# rev_n_v36.net
KiCad netlist of a schematic drawn in EAGLE
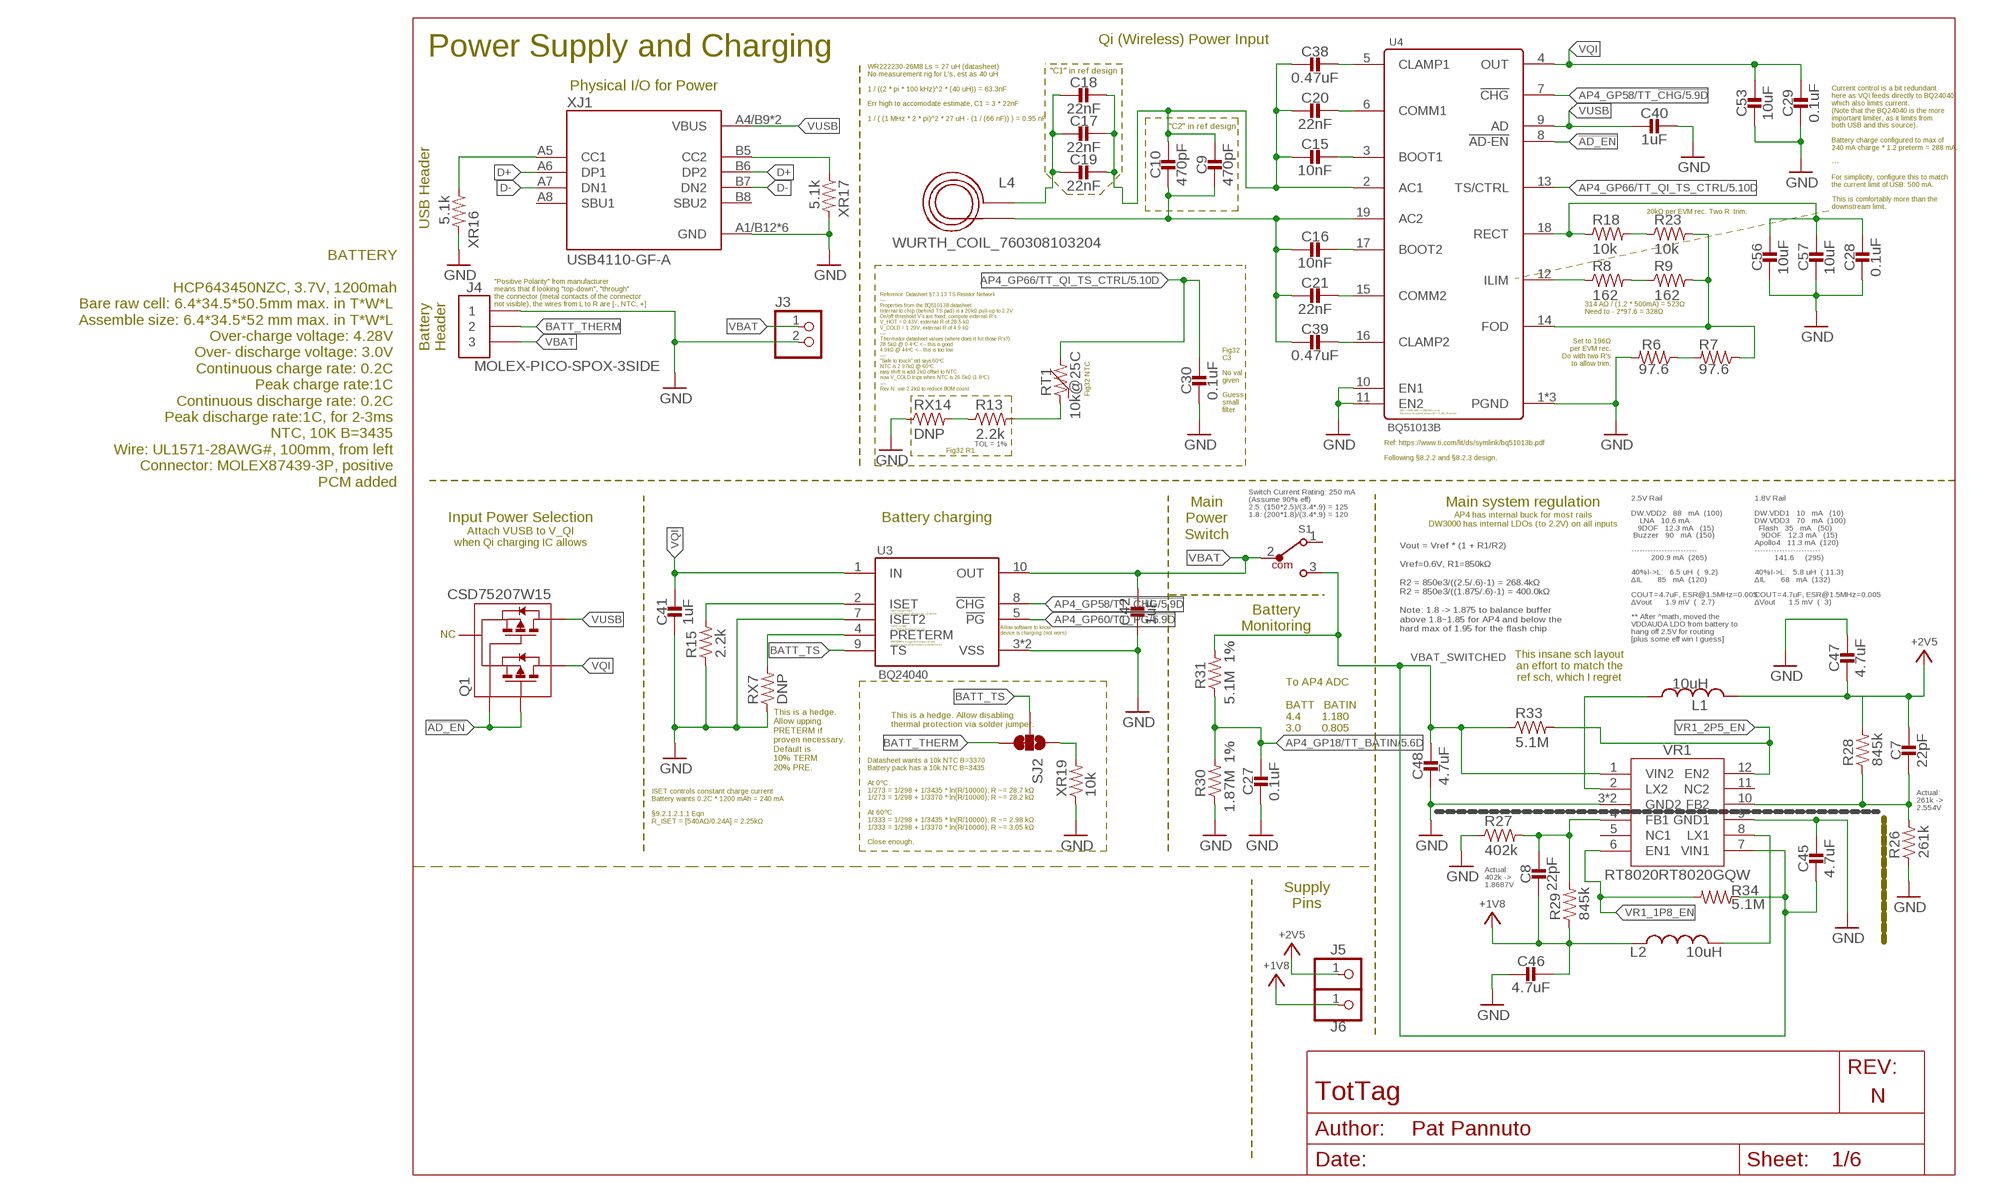
[diagram p0: schematic, sheet 1]
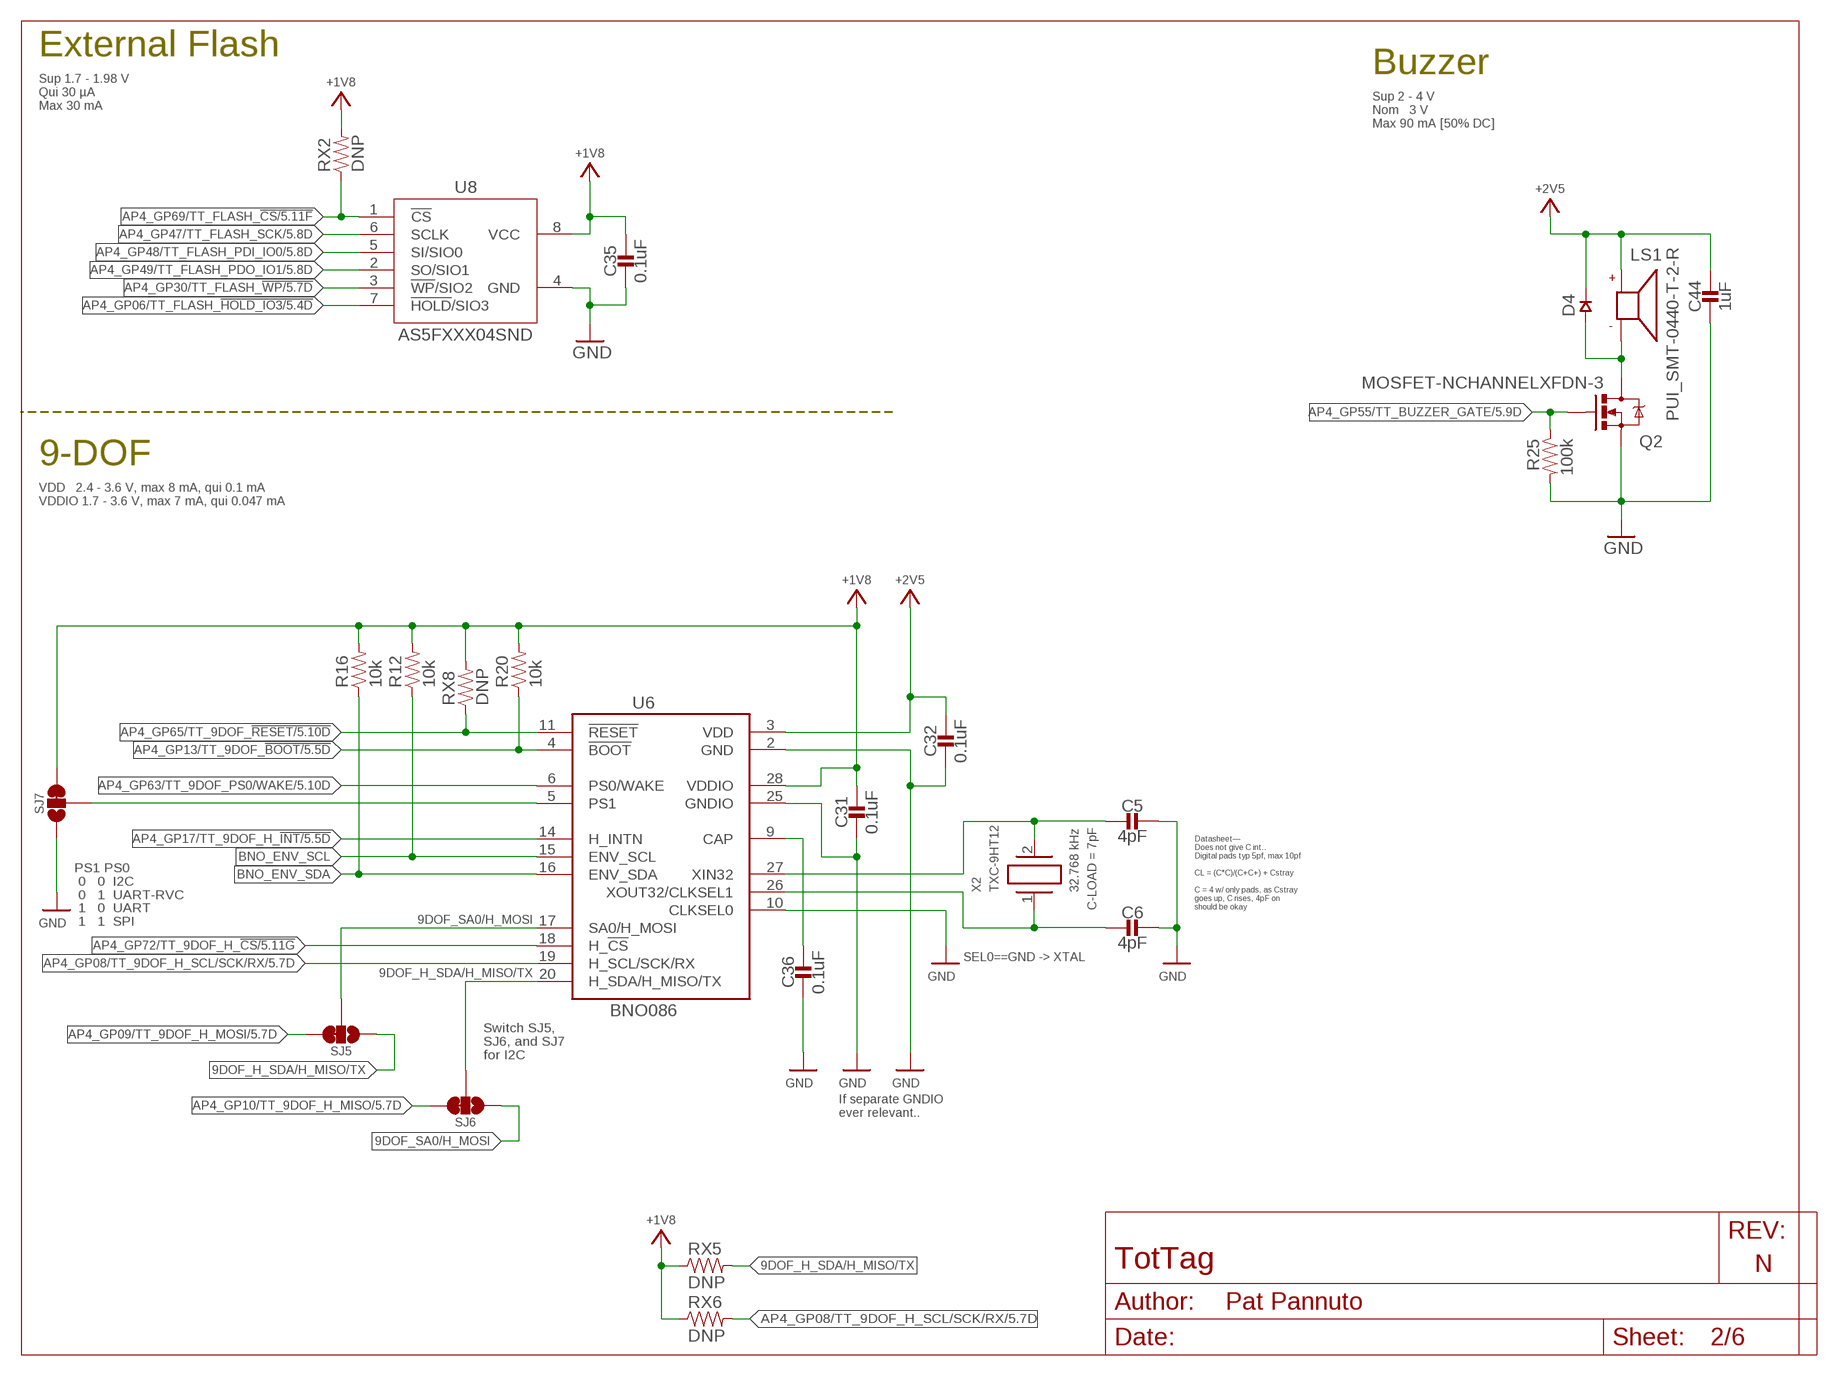
[diagram p1: schematic, sheet 2]
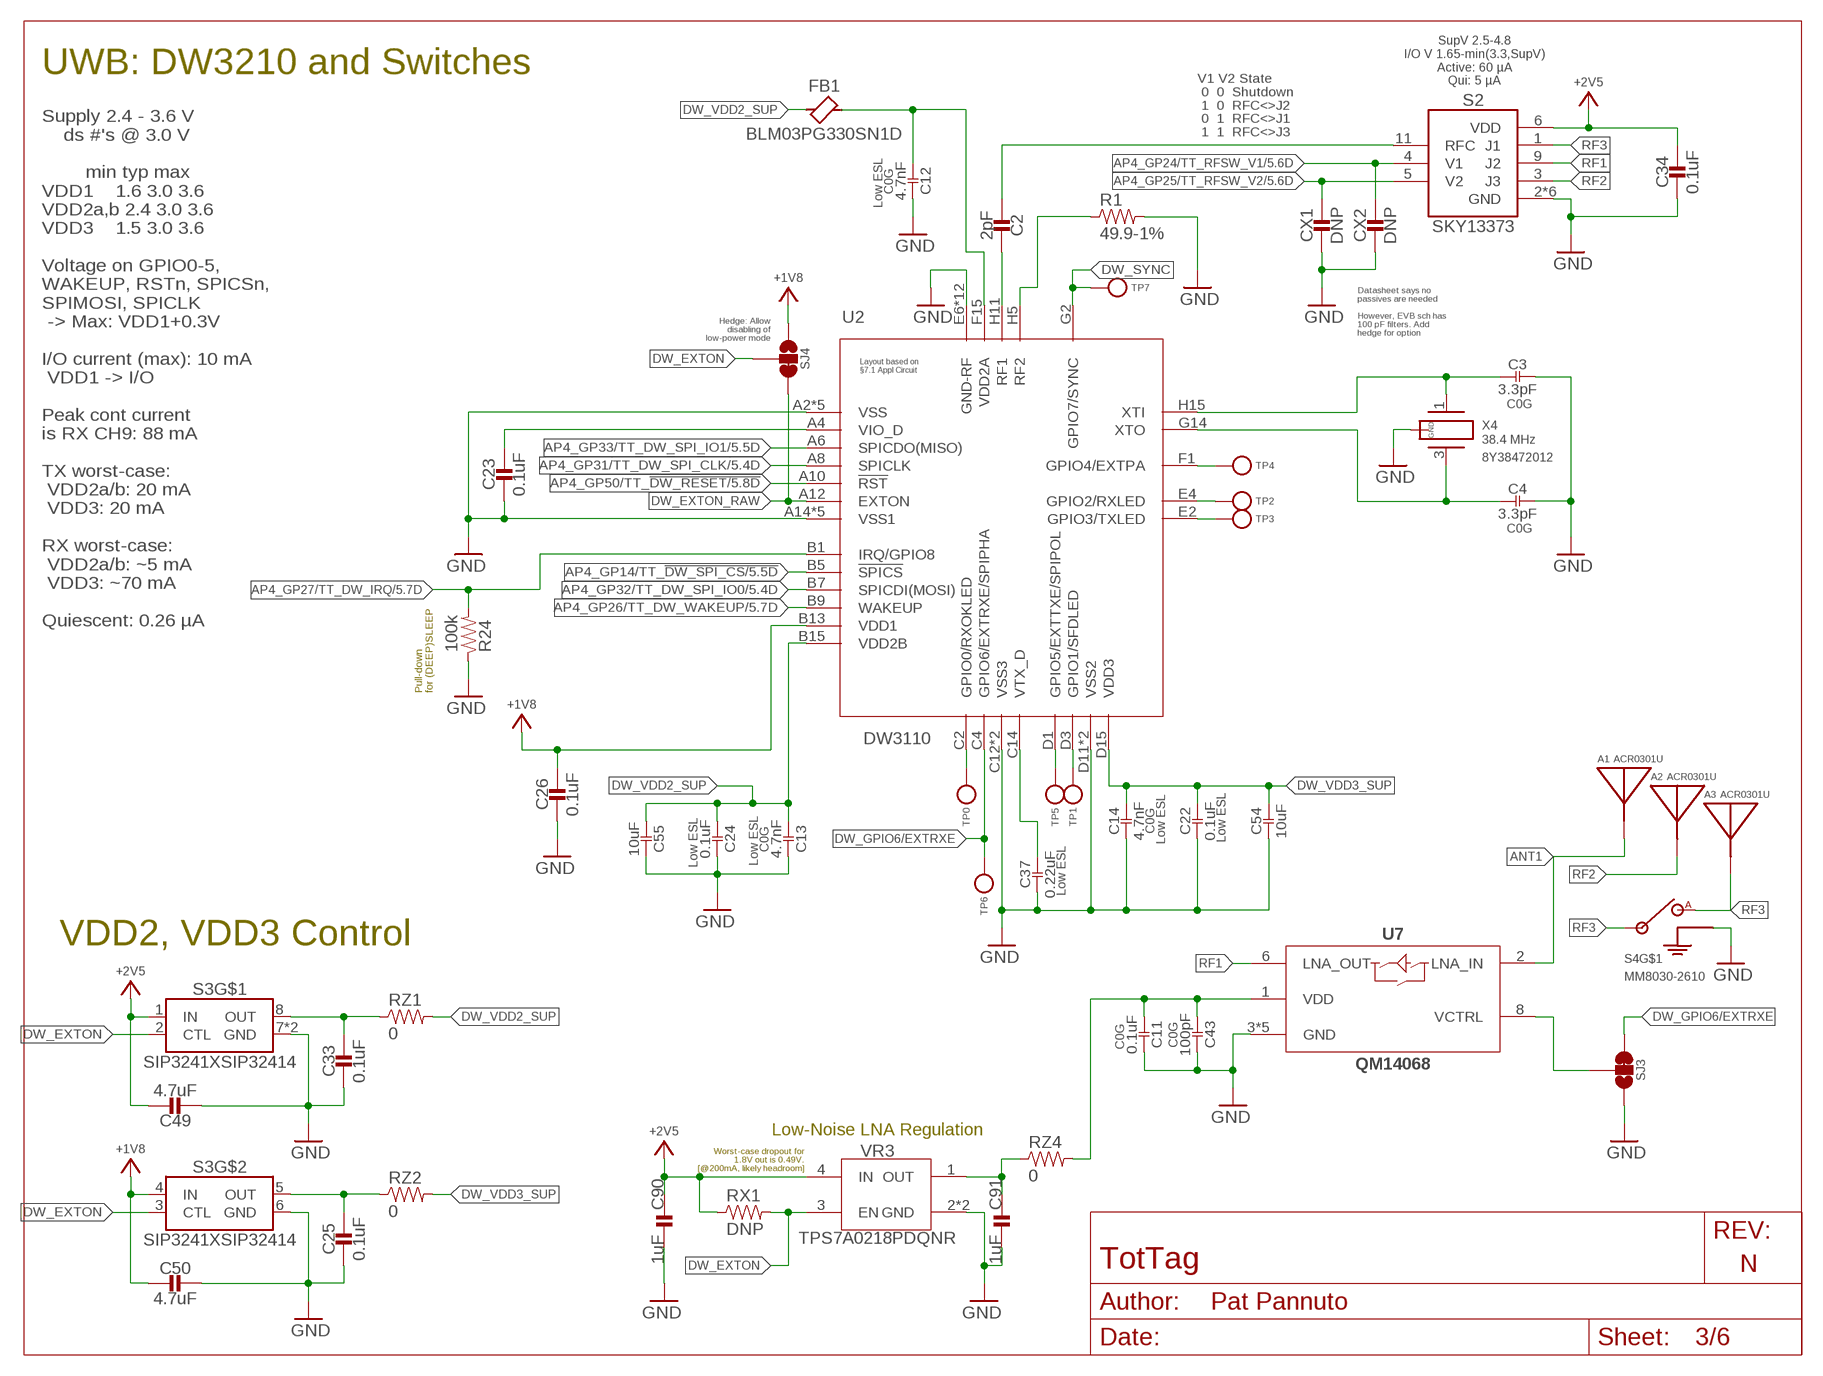
[diagram p2: schematic, sheet 3]
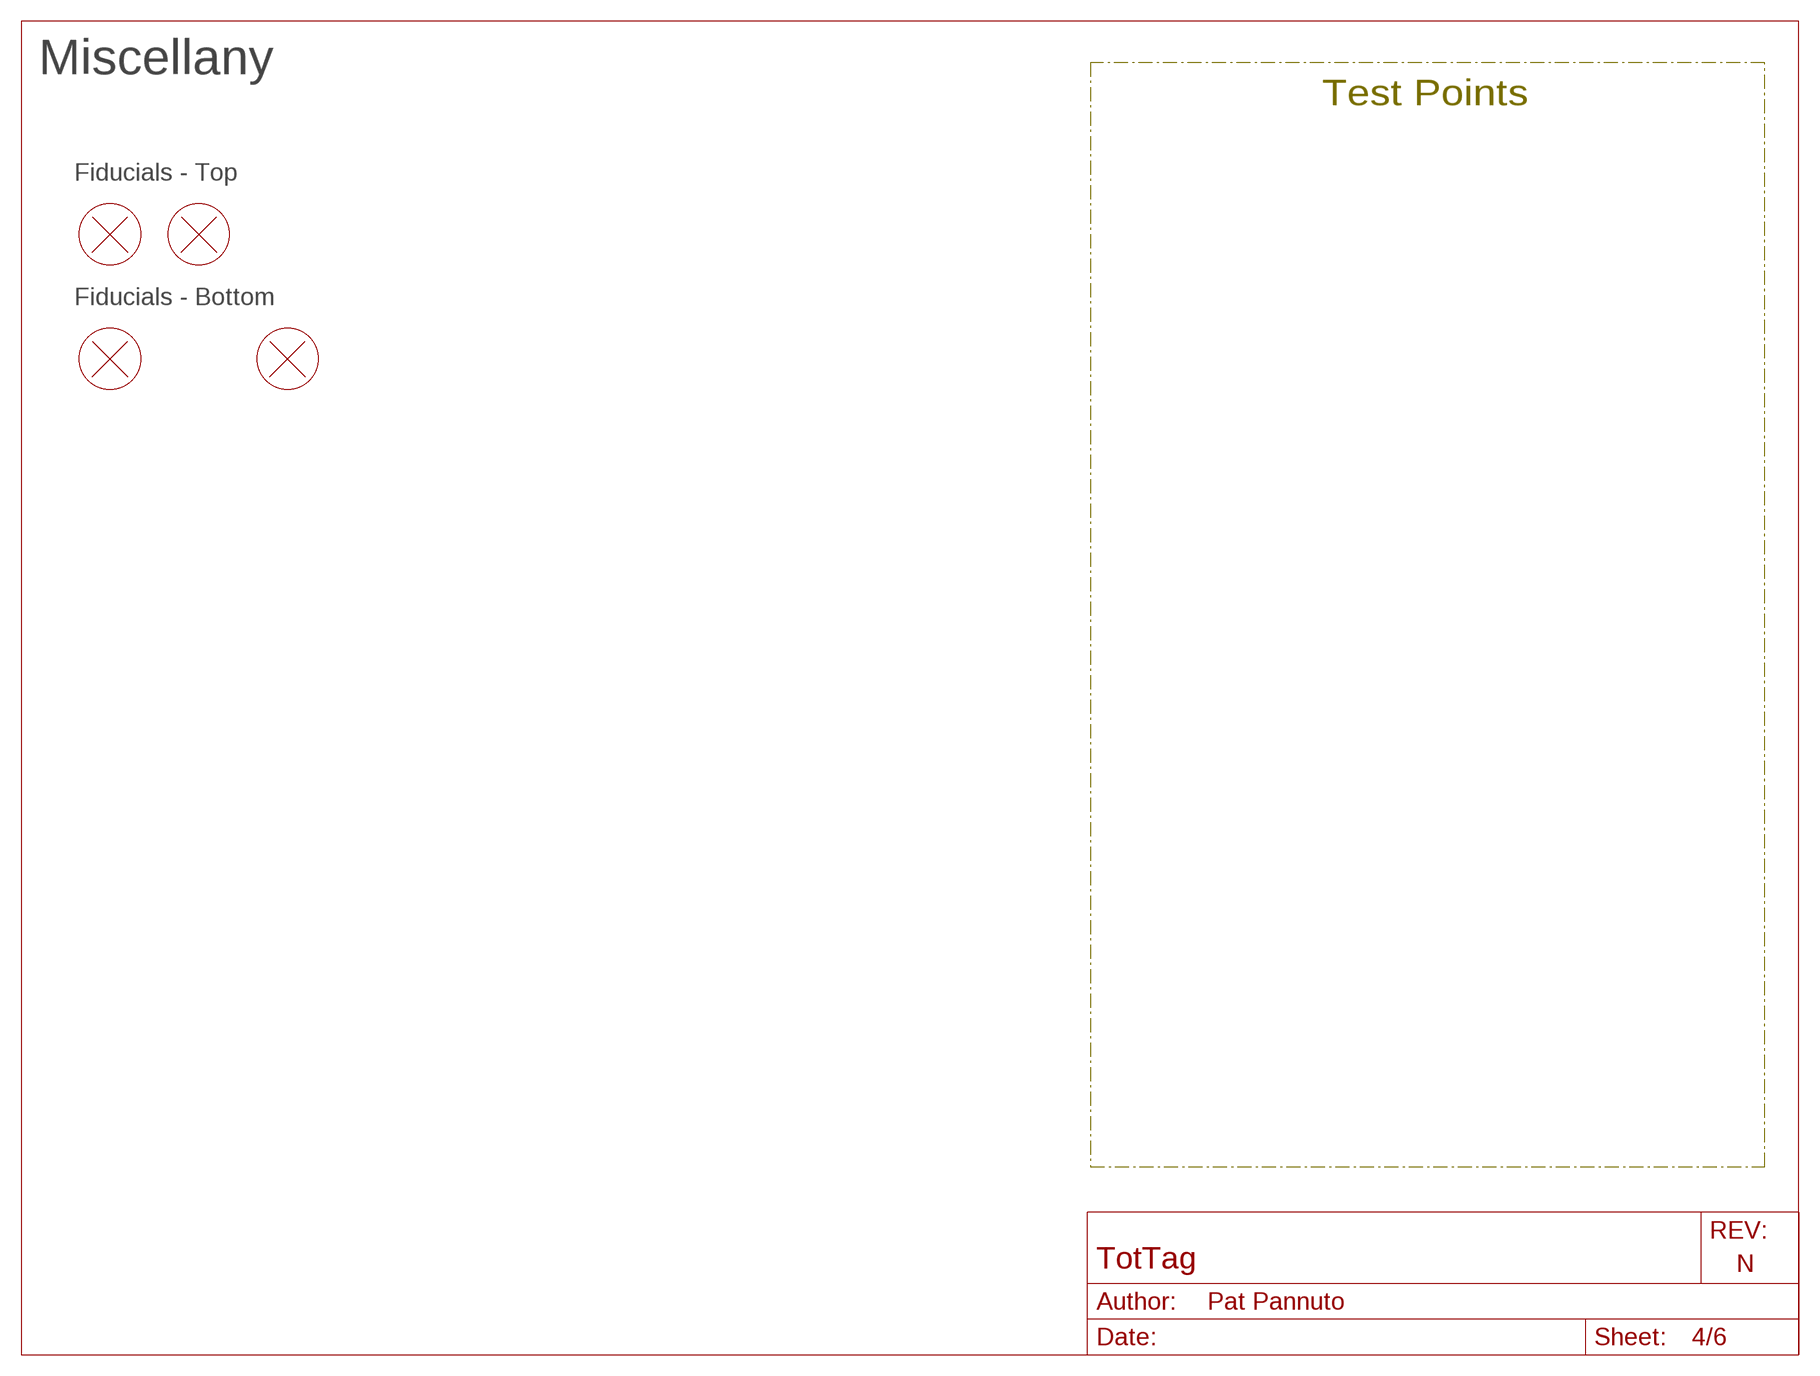
[diagram p3: schematic, sheet 4]
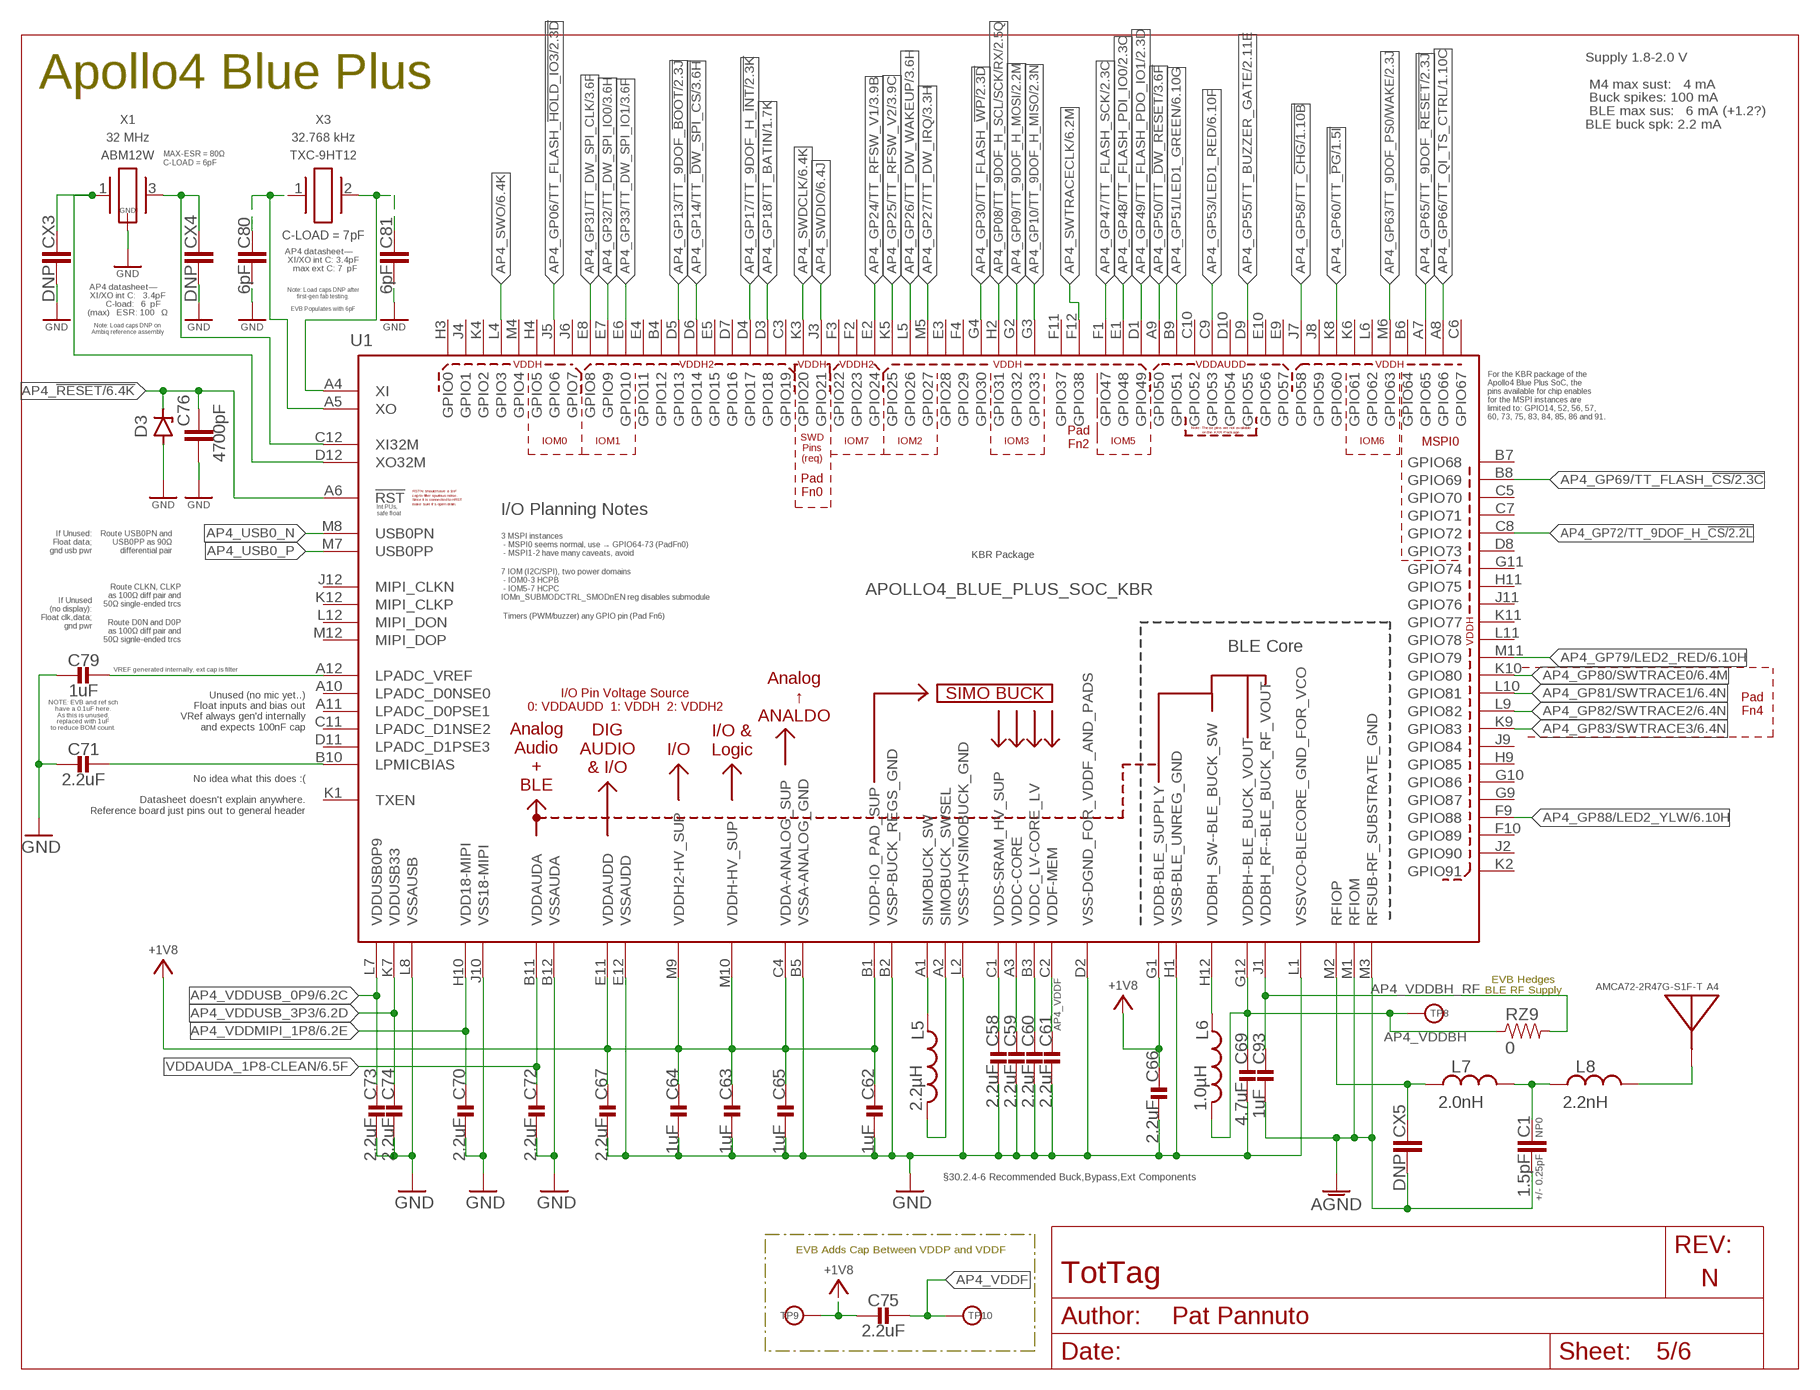
[diagram p4: schematic, sheet 5]
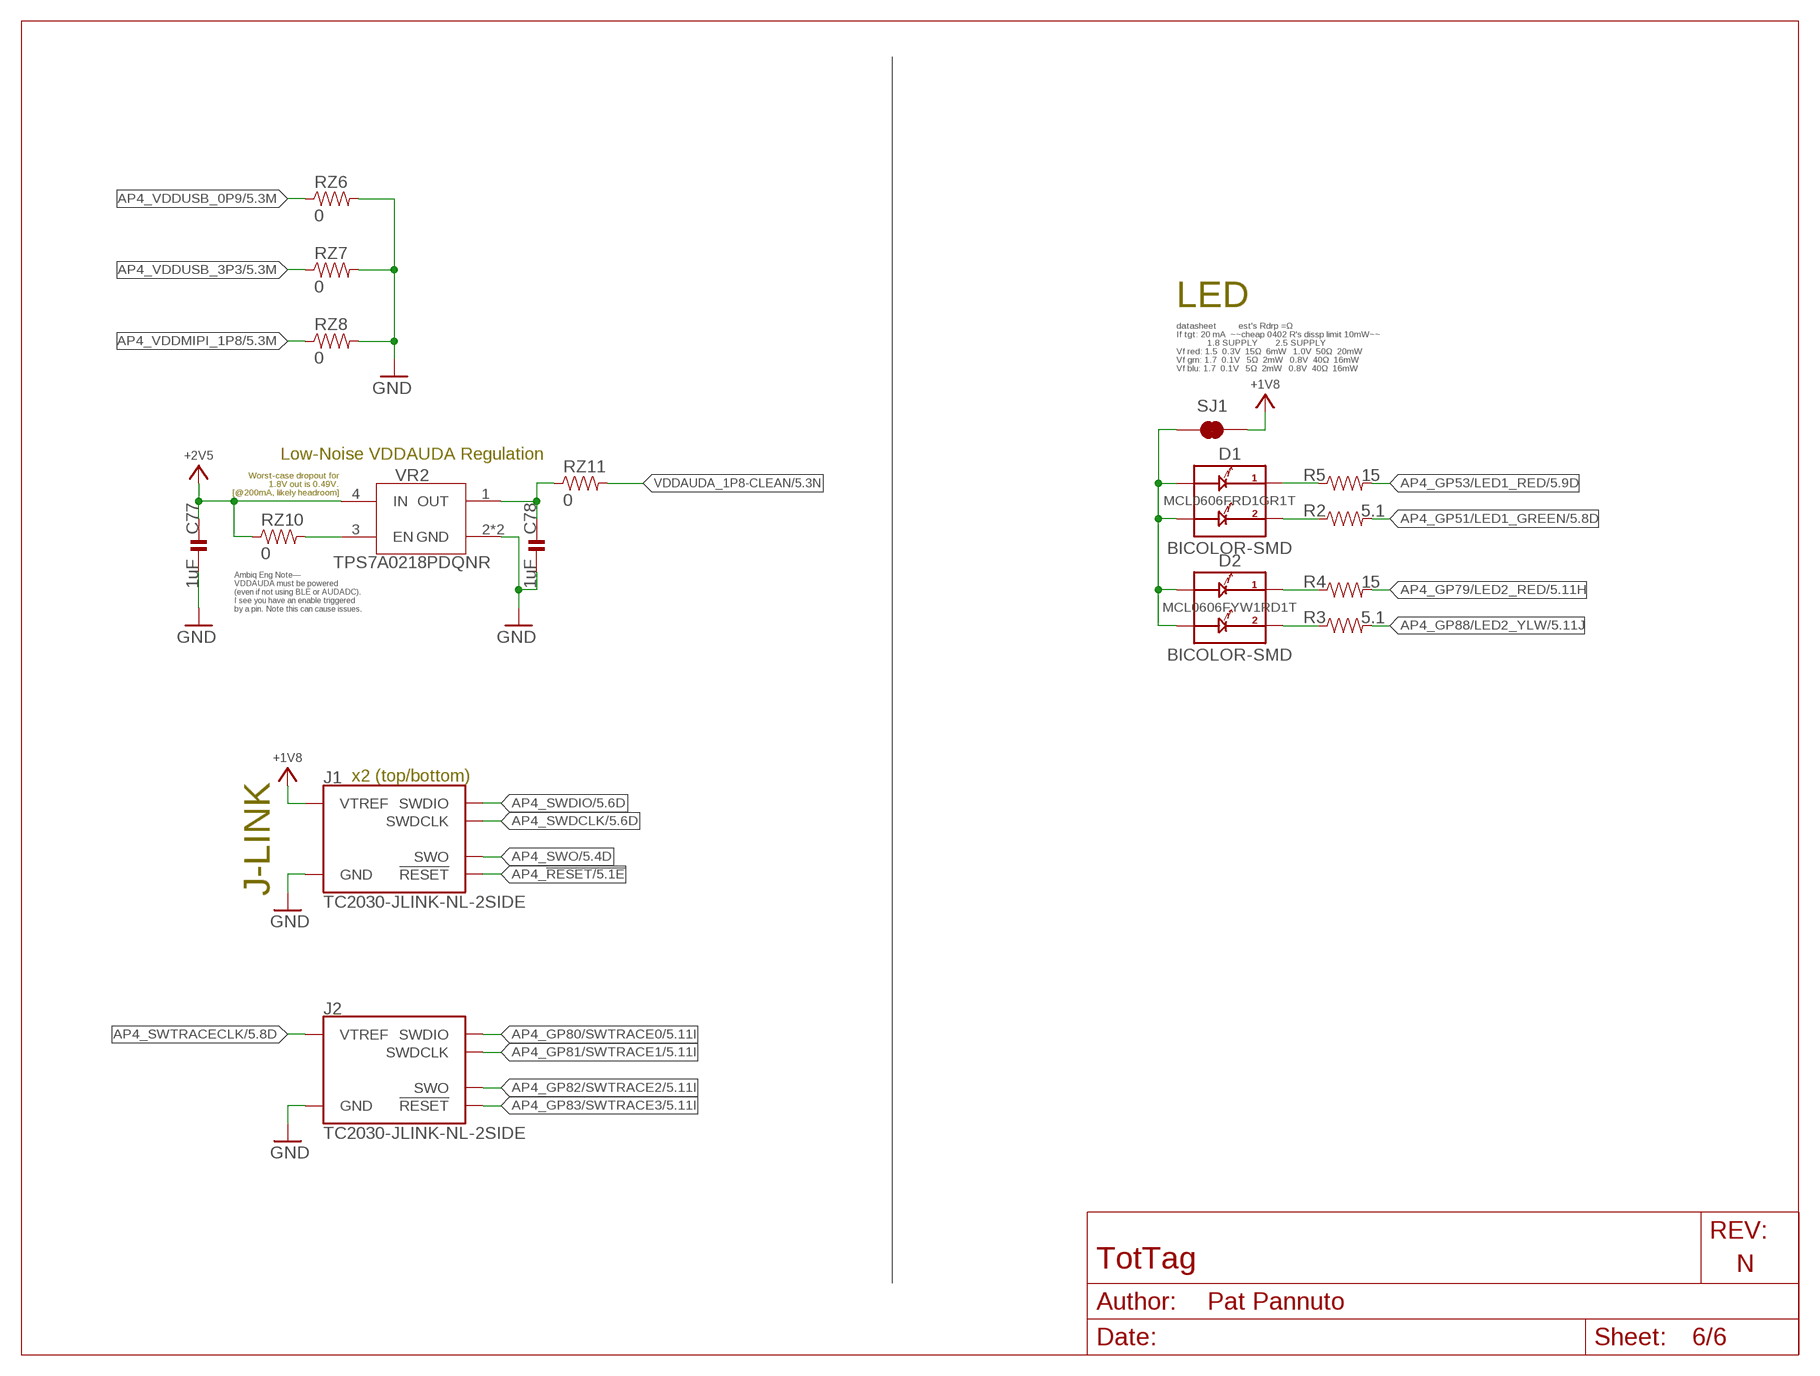
[diagram p5: schematic, sheet 6]

(export (version "E")
  (design (tool "Eeschema 10.0.6"))
  (components
    (comp (ref "C7")
      (value "22pF")
      (footprint "eagle-import:0201_CAP")
      (fields (field (name "MPN") "GRM0335C1H220FA01D"))
      (libsource (lib "eagle-import") (part "passives_20904581_CAPACITOR0201_CAP"))
    )
    (comp (ref "C8")
      (value "22pF")
      (footprint "eagle-import:0201_CAP")
      (fields (field (name "MPN") "GRM0335C1H220FA01D"))
      (libsource (lib "eagle-import") (part "passives_20904581_CAPACITOR0201_CAP"))
    )
    (comp (ref "C9")
      (value "470pF")
      (footprint "eagle-import:0402_CAP")
      (description "CAP CER 470PF 50V C0G/NP0 0402")
      (fields (field (name "MANUFACTURER") "Murata") (field (name "MPN") "GRM1555C1H471JA01J"))
      (libsource (lib "eagle-import") (part "passives_20904581_CAPACITOR0402_CAP"))
    )
    (comp (ref "C10")
      (value "470pF")
      (footprint "eagle-import:0402_CAP")
      (description "CAP CER 470PF 50V C0G/NP0 0402")
      (fields (field (name "MANUFACTURER") "Murata") (field (name "MPN") "GRM1555C1H471JA01J"))
      (libsource (lib "eagle-import") (part "passives_20904581_CAPACITOR0402_CAP"))
    )
    (comp (ref "C15")
      (value "10nF")
      (footprint "eagle-import:0402_CAP")
      (fields (field (name "MPN") "GRM155R71H103KA88J"))
      (libsource (lib "eagle-import") (part "passives_20904581_CAPACITOR0402_CAP"))
    )
    (comp (ref "C16")
      (value "10nF")
      (footprint "eagle-import:0402_CAP")
      (fields (field (name "MPN") "GRM155R71H103KA88J"))
      (libsource (lib "eagle-import") (part "passives_20904581_CAPACITOR0402_CAP"))
    )
    (comp (ref "C17")
      (value "22nF")
      (footprint "eagle-import:0402_CAP")
      (fields (field (name "MPN") "GRM155R71E223JA61D"))
      (libsource (lib "eagle-import") (part "passives_20904581_CAPACITOR0402_CAP"))
    )
    (comp (ref "C18")
      (value "22nF")
      (footprint "eagle-import:0402_CAP")
      (fields (field (name "MPN") "GRM155R71E223JA61D"))
      (libsource (lib "eagle-import") (part "passives_20904581_CAPACITOR0402_CAP"))
    )
    (comp (ref "C19")
      (value "22nF")
      (footprint "eagle-import:0402_CAP")
      (fields (field (name "MPN") "GRM155R71E223JA61D"))
      (libsource (lib "eagle-import") (part "passives_20904581_CAPACITOR0402_CAP"))
    )
    (comp (ref "C20")
      (value "22nF")
      (footprint "eagle-import:0402_CAP")
      (fields (field (name "MPN") "CC0402ZRY5V8BB223"))
      (libsource (lib "eagle-import") (part "passives_20904581_CAPACITOR0402_CAP"))
    )
    (comp (ref "C21")
      (value "22nF")
      (footprint "eagle-import:0402_CAP")
      (fields (field (name "MPN") "CC0402ZRY5V8BB223"))
      (libsource (lib "eagle-import") (part "passives_20904581_CAPACITOR0402_CAP"))
    )
    (comp (ref "C27")
      (value "0.1uF")
      (footprint "eagle-import:0402_CAP")
      (fields (field (name "MPN") "GRM155R71C104KA88J "))
      (libsource (lib "eagle-import") (part "CAPACITOR0402_CAP"))
    )
    (comp (ref "C28")
      (value "0.1uF")
      (footprint "eagle-import:0402_CAP")
      (fields (field (name "MPN") "GRM155R71C104KA88J "))
      (libsource (lib "eagle-import") (part "CAPACITOR0402_CAP"))
    )
    (comp (ref "C29")
      (value "0.1uF")
      (footprint "eagle-import:0402_CAP")
      (fields (field (name "MPN") "GRM155R71C104KA88J "))
      (libsource (lib "eagle-import") (part "CAPACITOR0402_CAP"))
    )
    (comp (ref "C30")
      (value "0.1uF")
      (footprint "eagle-import:0402_CAP")
      (fields (field (name "MPN") "GRM155R71C104KA88J "))
      (libsource (lib "eagle-import") (part "CAPACITOR0402_CAP"))
    )
    (comp (ref "C38")
      (value "0.47uF")
      (footprint "eagle-import:0402_CAP")
      (fields (field (name "MPN") "GRT155R61E474ME01D"))
      (libsource (lib "eagle-import") (part "passives_20904581_CAPACITOR0402_CAP"))
    )
    (comp (ref "C39")
      (value "0.47uF")
      (footprint "eagle-import:0402_CAP")
      (fields (field (name "MPN") "GRT155R61E474ME01D"))
      (libsource (lib "eagle-import") (part "passives_20904581_CAPACITOR0402_CAP"))
    )
    (comp (ref "C40")
      (value "1uF")
      (footprint "eagle-import:0402_CAP")
      (fields (field (name "MPN") "GRM155R70J105KA12J"))
      (libsource (lib "eagle-import") (part "CAPACITOR0402_CAP"))
    )
    (comp (ref "C41")
      (value "1uF")
      (footprint "eagle-import:0402_CAP")
      (fields (field (name "MPN") "GRM155R70J105KA12J"))
      (libsource (lib "eagle-import") (part "CAPACITOR0402_CAP"))
    )
    (comp (ref "C42")
      (value "1uF")
      (footprint "eagle-import:0402_CAP")
      (fields (field (name "MPN") "GRM155R70J105KA12J"))
      (libsource (lib "eagle-import") (part "CAPACITOR0402_CAP"))
    )
    (comp (ref "C45")
      (value "4.7uF")
      (footprint "eagle-import:0603_CAP")
      (fields (field (name "MPN") "C1608X7S1A475K080AC"))
      (libsource (lib "eagle-import") (part "passives_20904581_CAPACITOR0603_CAP"))
    )
    (comp (ref "C46")
      (value "4.7uF")
      (footprint "eagle-import:0603_CAP")
      (fields (field (name "MPN") "C1608X7S1A475K080AC"))
      (libsource (lib "eagle-import") (part "passives_20904581_CAPACITOR0603_CAP"))
    )
    (comp (ref "C47")
      (value "4.7uF")
      (footprint "eagle-import:0603_CAP")
      (fields (field (name "MPN") "C1608X7S1A475K080AC"))
      (libsource (lib "eagle-import") (part "passives_20904581_CAPACITOR0603_CAP"))
    )
    (comp (ref "C48")
      (value "4.7uF")
      (footprint "eagle-import:0603_CAP")
      (fields (field (name "MPN") "C1608X7S1A475K080AC"))
      (libsource (lib "eagle-import") (part "passives_20904581_CAPACITOR0603_CAP"))
    )
    (comp (ref "C53")
      (value "10uF")
      (footprint "eagle-import:0603_CAP")
      (fields (field (name "MPN") "CM105X5R106M25AT"))
      (libsource (lib "eagle-import") (part "passives_20904581_CAPACITOR0603_CAP"))
    )
    (comp (ref "C56")
      (value "10uF")
      (footprint "eagle-import:0603_CAP")
      (fields (field (name "MPN") "CM105X5R106M25AT"))
      (libsource (lib "eagle-import") (part "passives_20904581_CAPACITOR0603_CAP"))
    )
    (comp (ref "C57")
      (value "10uF")
      (footprint "eagle-import:0603_CAP")
      (fields (field (name "MPN") "CM105X5R106M25AT"))
      (libsource (lib "eagle-import") (part "passives_20904581_CAPACITOR0603_CAP"))
    )
    (comp (ref "J3")
      (value "PINHD-1X2")
      (footprint "eagle-import:1X02")
      (libsource (lib "eagle-import") (part "PINHD-1X2"))
    )
    (comp (ref "J4")
      (value "MOLEX-PICO-SPOX-3SIDE")
      (footprint "eagle-import:MOLEX-PICO-SPOX-3_SIDE")
      (libsource (lib "eagle-import") (part "MOLEX-PICO-SPOX-3SIDE"))
    )
    (comp (ref "J5")
      (value "PINHD-1X1")
      (footprint "eagle-import:1X01")
      (libsource (lib "eagle-import") (part "PINHD-1X1"))
    )
    (comp (ref "J6")
      (value "PINHD-1X1")
      (footprint "eagle-import:1X01")
      (libsource (lib "eagle-import") (part "PINHD-1X1"))
    )
    (comp (ref "L1")
      (value "10uH")
      (footprint "eagle-import:NRX3015")
      (fields (field (name "MANUFACTURER") "TAIYO YUDEN") (field (name "MPN") "NR3015T100M"))
      (libsource (lib "eagle-import") (part "INDUCTORNRX3015"))
    )
    (comp (ref "L2")
      (value "10uH")
      (footprint "eagle-import:NRX3015")
      (fields (field (name "MANUFACTURER") "TAIYO YUDEN") (field (name "MPN") "NR3015T100M"))
      (libsource (lib "eagle-import") (part "INDUCTORNRX3015"))
    )
    (comp (ref "L4")
      (value "WURTH_COIL_760308103204")
      (footprint "eagle-import:WURTH_COIL_760308103204")
      (fields (field (name "MANUFACTURER") "Würth Elektronik") (field (name "MPN") "760308103204"))
      (libsource (lib "eagle-import") (part "WURTH_COIL_760308103204"))
    )
    (comp (ref "Q1")
      (value "CSD75207W15")
      (footprint "eagle-import:DSBGA")
      (fields (field (name "MANUFACTURER") "TEXAS INSTRUMENTS"))
      (libsource (lib "eagle-import") (part "CSD75207W15"))
    )
    (comp (ref "R6")
      (value "97.6")
      (footprint "eagle-import:0402_RES")
      (fields (field (name "MPN") "RMCF0402FT97R6"))
      (libsource (lib "eagle-import") (part "passives_20904581_RESISTOR0402_RES"))
    )
    (comp (ref "R7")
      (value "97.6")
      (footprint "eagle-import:0402_RES")
      (fields (field (name "MPN") "RMCF0402FT97R6"))
      (libsource (lib "eagle-import") (part "passives_20904581_RESISTOR0402_RES"))
    )
    (comp (ref "R8")
      (value "162")
      (footprint "eagle-import:0402_RES")
      (fields (field (name "MPN") "RMCF0402FT162R"))
      (libsource (lib "eagle-import") (part "passives_20904581_RESISTOR0402_RES"))
    )
    (comp (ref "R9")
      (value "162")
      (footprint "eagle-import:0402_RES")
      (fields (field (name "MPN") "RMCF0402FT162R"))
      (libsource (lib "eagle-import") (part "passives_20904581_RESISTOR0402_RES"))
    )
    (comp (ref "R13")
      (value "2.2k")
      (footprint "eagle-import:0402_RES")
      (fields (field (name "MPN") "RC0402FR-072K2L") (field (name "TOL") "1%"))
      (libsource (lib "eagle-import") (part "RESISTOR0402_RES"))
    )
    (comp (ref "R15")
      (value "2.2k")
      (footprint "eagle-import:0402_RES")
      (fields (field (name "MPN") "RC0402FR-072K2L"))
      (libsource (lib "eagle-import") (part "passives_20904581_RESISTOR0402_RES"))
    )
    (comp (ref "R18")
      (value "10k")
      (footprint "eagle-import:0402_RES")
      (fields (field (name "MPN") "RC0402JR-0710KL"))
      (libsource (lib "eagle-import") (part "RESISTOR0402_RES"))
    )
    (comp (ref "R23")
      (value "10k")
      (footprint "eagle-import:0402_RES")
      (fields (field (name "MPN") "RC0402JR-0710KL"))
      (libsource (lib "eagle-import") (part "RESISTOR0402_RES"))
    )
    (comp (ref "R26")
      (value "261k")
      (footprint "eagle-import:0201_RES")
      (fields (field (name "MPN") "ERJ-1GNF2613C"))
      (libsource (lib "eagle-import") (part "passives_20904581_RESISTOR0201_RES"))
    )
    (comp (ref "R27")
      (value "402k")
      (footprint "eagle-import:0201_RES")
      (fields (field (name "MPN") "ERJ-1GNF4023C"))
      (libsource (lib "eagle-import") (part "passives_20904581_RESISTOR0201_RES"))
    )
    (comp (ref "R28")
      (value "845k")
      (footprint "eagle-import:0201_RES")
      (fields (field (name "MPN") "ERJ-1GNF8453C"))
      (libsource (lib "eagle-import") (part "passives_20904581_RESISTOR0201_RES"))
    )
    (comp (ref "R29")
      (value "845k")
      (footprint "eagle-import:0201_RES")
      (fields (field (name "MPN") "ERJ-1GNF8453C"))
      (libsource (lib "eagle-import") (part "passives_20904581_RESISTOR0201_RES"))
    )
    (comp (ref "R30")
      (value "1.87M")
      (footprint "eagle-import:0402_RES")
      (fields (field (name "MPN") "RMCF0402FT1M87") (field (name "TOLERANCE") "1%"))
      (libsource (lib "eagle-import") (part "RESISTOR0402_RES"))
    )
    (comp (ref "R31")
      (value "5.1M")
      (footprint "eagle-import:0402_RES")
      (fields (field (name "MPN") "RMCF0402FT5M10") (field (name "TOLERANCE") "1%"))
      (libsource (lib "eagle-import") (part "RESISTOR0402_RES"))
    )
    (comp (ref "R33")
      (value "5.1M")
      (footprint "eagle-import:0402_RES")
      (fields (field (name "MPN") "RMCF0402FT5M10"))
      (libsource (lib "eagle-import") (part "RESISTOR0402_RES"))
    )
    (comp (ref "R34")
      (value "5.1M")
      (footprint "eagle-import:0402_RES")
      (fields (field (name "MPN") "RMCF0402FT5M10"))
      (libsource (lib "eagle-import") (part "RESISTOR0402_RES"))
    )
    (comp (ref "RT1")
      (value "10k@25C")
      (footprint "eagle-import:0402_RES")
      (fields (field (name "MPN") "NCU15XH103F60RC"))
      (libsource (lib "eagle-import") (part "THERMISTOR0402"))
    )
    (comp (ref "RX7")
      (value "DNP")
      (footprint "eagle-import:0402_RES")
      (libsource (lib "eagle-import") (part "passives_20904581_RESISTOR0402_RES"))
    )
    (comp (ref "RX14")
      (value "DNP")
      (footprint "eagle-import:0402_RES")
      (libsource (lib "eagle-import") (part "RESISTOR0402_RES"))
    )
    (comp (ref "S1")
      (value "450404015514")
      (footprint "eagle-import:450404015514")
      (libsource (lib "eagle-import") (part "450404015514"))
    )
    (comp (ref "SJ2")
      (value "JUMPER-SMT_3_1-NC_TRACE_SILK")
      (footprint "eagle-import:SMT-JUMPER_3_1-NC_TRACE_SILK")
      (libsource (lib "eagle-import") (part "JUMPER-SMT_3_1-NC_TRACE_SILK"))
    )
    (comp (ref "U3")
      (value "BQ24040")
      (footprint "eagle-import:DSQ0010A")
      (fields (field (name "MPN") "BQ24040DSQR"))
      (libsource (lib "eagle-import") (part "BQ24040"))
    )
    (comp (ref "U4")
      (value "BQ51013B")
      (footprint "eagle-import:RHL0020A")
      (fields (field (name "MPN") "BQ51013BRHLR"))
      (libsource (lib "eagle-import") (part "BQ51013B"))
    )
    (comp (ref "VR1")
      (value "RT8020RT8020GQW")
      (footprint "eagle-import:SON45P300X300X80-13T160X250N")
      (fields (field (name "MANUFACTURER") "RichTek") (field (name "MPN") "RT8020GQW"))
      (libsource (lib "eagle-import") (part "RT8020RT8020GQW"))
    )
    (comp (ref "XJ1")
      (value "USB4110-GF-A")
      (footprint "eagle-import:GCT_USB4110-GF-A")
      (fields (field (name "MF") "GCT"))
      (libsource (lib "eagle-import") (part "USB4110-GF-A"))
    )
    (comp (ref "XR16")
      (value "5.1k")
      (footprint "eagle-import:0402_RES")
      (fields (field (name "MPN") "RMCF0402FT5K10"))
      (libsource (lib "eagle-import") (part "passives_20904581_RESISTOR0402_RES"))
    )
    (comp (ref "XR17")
      (value "5.1k")
      (footprint "eagle-import:0402_RES")
      (fields (field (name "MPN") "RMCF0402FT5K10"))
      (libsource (lib "eagle-import") (part "passives_20904581_RESISTOR0402_RES"))
    )
    (comp (ref "XR19")
      (value "10k")
      (footprint "eagle-import:0402_RES")
      (fields (field (name "MPN") "RC0402JR-0710KL"))
      (libsource (lib "eagle-import") (part "RESISTOR0402_RES"))
    )
    (comp (ref "FD1")
      (value "FIDUCIAL")
      (footprint "eagle-import:FIDUCIAL_1MM-CU_2MM-MASK")
      (libsource (lib "eagle-import") (part "FIDUCIAL"))
    )
    (comp (ref "FD2")
      (value "FIDUCIAL")
      (footprint "eagle-import:FIDUCIAL_1MM-CU_2MM-MASK")
      (libsource (lib "eagle-import") (part "FIDUCIAL"))
    )
    (comp (ref "FD4")
      (value "FIDUCIAL")
      (footprint "eagle-import:FIDUCIAL_1MM-CU_2MM-MASK")
      (libsource (lib "eagle-import") (part "FIDUCIAL"))
    )
    (comp (ref "FD6")
      (value "FIDUCIAL")
      (footprint "eagle-import:FIDUCIAL_1MM-CU_2MM-MASK")
      (libsource (lib "eagle-import") (part "FIDUCIAL"))
    )
    (comp (ref "A4")
      (value "AMCA72-2R47G-S1F-T")
      (footprint "eagle-import:AMCA72-2R470G-S1F-T")
      (fields (field (name "MPN") "AMCA72-2R470G-S1F-T4"))
      (libsource (lib "eagle-import") (part "AMCA72-2R47G-S1F-T"))
    )
    (comp (ref "C1")
      (value "1.5pF")
      (footprint "eagle-import:CAPC1005X60")
      (description "CAP CER 1.5PF 50V C0G/NP0 0402")
      (fields
        (field (name "MANUFACTURER") "KEMET")
        (field (name "MPN") "C0402C159C5GACTU")
        (field (name "TEMPCOEFF") "NP0")
        (field (name "TOLERANCE") "+/- 0.25pF")
      )
      (libsource (lib "eagle-import") (part "CCHIP-0402(1005-METRIC)_"))
    )
    (comp (ref "C58")
      (value "2.2uF")
      (footprint "eagle-import:0201_CAP")
      (fields (field (name "MANUFACTURER") "Murata") (field (name "MPN") "GRM033R61A225KE47D"))
      (libsource (lib "eagle-import") (part "passives_20904581_CAPACITOR0201_CAP"))
    )
    (comp (ref "C59")
      (value "2.2uF")
      (footprint "eagle-import:0201_CAP")
      (fields (field (name "MANUFACTURER") "Murata") (field (name "MPN") "GRM033R61A225KE47D"))
      (libsource (lib "eagle-import") (part "passives_20904581_CAPACITOR0201_CAP"))
    )
    (comp (ref "C60")
      (value "2.2uF")
      (footprint "eagle-import:0201_CAP")
      (fields (field (name "MANUFACTURER") "Murata") (field (name "MPN") "GRM033R61A225KE47D"))
      (libsource (lib "eagle-import") (part "passives_20904581_CAPACITOR0201_CAP"))
    )
    (comp (ref "C61")
      (value "2.2uF")
      (footprint "eagle-import:0201_CAP")
      (fields (field (name "MANUFACTURER") "Murata") (field (name "MPN") "GRM033R61A225KE47D"))
      (libsource (lib "eagle-import") (part "passives_20904581_CAPACITOR0201_CAP"))
    )
    (comp (ref "C62")
      (value "1uF")
      (footprint "eagle-import:0201_CAP")
      (fields (field (name "MANUFACTURER") "Murata") (field (name "MPN") "GRM033R61A105ME44D"))
      (libsource (lib "eagle-import") (part "passives_20904581_CAPACITOR0201_CAP"))
    )
    (comp (ref "C63")
      (value "1uF")
      (footprint "eagle-import:0201_CAP")
      (fields (field (name "MANUFACTURER") "Murata") (field (name "MPN") "GRM033R61A105ME44D"))
      (libsource (lib "eagle-import") (part "passives_20904581_CAPACITOR0201_CAP"))
    )
    (comp (ref "C64")
      (value "1uF")
      (footprint "eagle-import:0201_CAP")
      (fields (field (name "MANUFACTURER") "Murata") (field (name "MPN") "GRM033R61A105ME44D"))
      (libsource (lib "eagle-import") (part "passives_20904581_CAPACITOR0201_CAP"))
    )
    (comp (ref "C65")
      (value "1uF")
      (footprint "eagle-import:0201_CAP")
      (fields (field (name "MANUFACTURER") "Murata") (field (name "MPN") "GRM033R61A105ME44D"))
      (libsource (lib "eagle-import") (part "passives_20904581_CAPACITOR0201_CAP"))
    )
    (comp (ref "C66")
      (value "2.2uF")
      (footprint "eagle-import:0201_CAP")
      (fields (field (name "MANUFACTURER") "Murata") (field (name "MPN") "GRM033R61A225KE47D"))
      (libsource (lib "eagle-import") (part "passives_20904581_CAPACITOR0201_CAP"))
    )
    (comp (ref "C67")
      (value "2.2uF")
      (footprint "eagle-import:0201_CAP")
      (fields (field (name "MANUFACTURER") "Murata") (field (name "MPN") "GRM033R61A225KE47D"))
      (libsource (lib "eagle-import") (part "passives_20904581_CAPACITOR0201_CAP"))
    )
    (comp (ref "C69")
      (value "4.7uF")
      (footprint "eagle-import:0402_CAP")
      (fields (field (name "MPN") "CL05A475MP5NRNC"))
      (libsource (lib "eagle-import") (part "CAPACITOR0402_CAP"))
    )
    (comp (ref "C70")
      (value "2.2uF")
      (footprint "eagle-import:0201_CAP")
      (fields (field (name "MANUFACTURER") "Murata") (field (name "MPN") "GRM033R61A225KE47D"))
      (libsource (lib "eagle-import") (part "passives_20904581_CAPACITOR0201_CAP"))
    )
    (comp (ref "C71")
      (value "2.2uF")
      (footprint "eagle-import:0201_CAP")
      (fields (field (name "MANUFACTURER") "Murata") (field (name "MPN") "GRM033R61A225KE47D"))
      (libsource (lib "eagle-import") (part "passives_20904581_CAPACITOR0201_CAP"))
    )
    (comp (ref "C72")
      (value "2.2uF")
      (footprint "eagle-import:0201_CAP")
      (fields (field (name "MANUFACTURER") "Murata") (field (name "MPN") "GRM033R61A225KE47D"))
      (libsource (lib "eagle-import") (part "passives_20904581_CAPACITOR0201_CAP"))
    )
    (comp (ref "C73")
      (value "2.2uF")
      (footprint "eagle-import:0201_CAP")
      (fields (field (name "MANUFACTURER") "Murata") (field (name "MPN") "GRM033R61A225KE47D"))
      (libsource (lib "eagle-import") (part "passives_20904581_CAPACITOR0201_CAP"))
    )
    (comp (ref "C74")
      (value "2.2uF")
      (footprint "eagle-import:0201_CAP")
      (fields (field (name "MANUFACTURER") "Murata") (field (name "MPN") "GRM033R61A225KE47D"))
      (libsource (lib "eagle-import") (part "passives_20904581_CAPACITOR0201_CAP"))
    )
    (comp (ref "C75")
      (value "2.2uF")
      (footprint "eagle-import:0201_CAP")
      (fields (field (name "MANUFACTURER") "Murata") (field (name "MPN") "GRM033R61A225KE47D"))
      (libsource (lib "eagle-import") (part "passives_20904581_CAPACITOR0201_CAP"))
    )
    (comp (ref "C76")
      (value "4700pF")
      (footprint "eagle-import:CAPC1005X60")
      (fields (field (name "MPN") "KGM05AR71E472KH"))
      (libsource (lib "eagle-import") (part "CCHIP-0402(1005-METRIC)_"))
    )
    (comp (ref "C79")
      (value "1uF")
      (footprint "eagle-import:0201_CAP")
      (fields (field (name "MANUFACTURER") "MURATA") (field (name "MPN") "GRM033R61A105ME44D"))
      (libsource (lib "eagle-import") (part "passives_20904581_CAPACITOR0201_CAP"))
    )
    (comp (ref "C80")
      (value "6pF")
      (footprint "eagle-import:CAPC1005X60")
      (fields (field (name "MANUFACTURER") "Murata") (field (name "MPN") "GCM1555C1H6R0BA16D"))
      (libsource (lib "eagle-import") (part "CCHIP-0402(1005-METRIC)_"))
    )
    (comp (ref "C81")
      (value "6pF")
      (footprint "eagle-import:CAPC1005X60")
      (fields (field (name "MANUFACTURER") "Murata") (field (name "MPN") "GCM1555C1H6R0BA16D"))
      (libsource (lib "eagle-import") (part "CCHIP-0402(1005-METRIC)_"))
    )
    (comp (ref "C93")
      (value "1uF")
      (footprint "eagle-import:0201_CAP")
      (fields (field (name "MANUFACTURER") "Murata") (field (name "MPN") "GRM033R61A105ME44D"))
      (libsource (lib "eagle-import") (part "passives_20904581_CAPACITOR0201_CAP"))
    )
    (comp (ref "CX3")
      (value "DNP")
      (footprint "eagle-import:CAPC1005X60")
      (libsource (lib "eagle-import") (part "CCHIP-0402(1005-METRIC)_"))
    )
    (comp (ref "CX4")
      (value "DNP")
      (footprint "eagle-import:CAPC1005X60")
      (libsource (lib "eagle-import") (part "CCHIP-0402(1005-METRIC)_"))
    )
    (comp (ref "CX5")
      (value "DNP")
      (footprint "eagle-import:CAPC1005X60")
      (libsource (lib "eagle-import") (part "CCHIP-0402(1005-METRIC)_"))
    )
    (comp (ref "D3")
      (value "ZENER")
      (footprint "eagle-import:SODFL1608X70")
      (description "DIODE TVS 5.5V STANDOFF 8V BREAKDOWN SC79")
      (fields (field (name "MANUFACTURER") "NXP SEMICONDUCTOR") (field (name "MPN") "PESD5V0X1UB,135"))
      (libsource (lib "eagle-import") (part "ZENERSODFL(1608-METRIC)_"))
    )
    (comp (ref "L5")
      (value "2.2µH")
      (footprint "eagle-import:0805_CAP")
      (fields (field (name "MANUFACTURER") "Murata") (field (name "MPN") "DFE201210U-2R2M=P2"))
      (libsource (lib "eagle-import") (part "INDUCTOR0805"))
    )
    (comp (ref "L6")
      (value "1.0µH")
      (footprint "eagle-import:0603_CAP")
      (fields (field (name "MANUFACTURER") "Murata") (field (name "MPN") "DFE18SAN1R0ME0L"))
      (libsource (lib "eagle-import") (part "INDUCTOR0603"))
    )
    (comp (ref "L7")
      (value "2.0nH")
      (footprint "eagle-import:INDC1006X60N")
      (description "FIXED IND 2.0NH0.1NH SMD")
      (fields
        (field (name "MANUFACTURER") "Murata")
        (field (name "MPN") "LQG15HS2N0B02D")
        (field (name "TOLERANCE") "+/- 0.1 nH")
      )
      (libsource (lib "eagle-import") (part "LCHIP-0402(1006-METRIC)_"))
    )
    (comp (ref "L8")
      (value "2.2nH")
      (footprint "eagle-import:INDC1006X60N")
      (description "FIXED IND 2.2NH0.1NH SMD")
      (fields
        (field (name "MANUFACTURER") "Murata")
        (field (name "MPN") "LQG15HN2N2B02D")
        (field (name "TOLERANCE") "+/- 0.1 nH")
      )
      (libsource (lib "eagle-import") (part "LCHIP-0402(1006-METRIC)_"))
    )
    (comp (ref "RZ9")
      (value "0")
      (footprint "eagle-import:0402_RES")
      (fields (field (name "MPN") "RMCF0402ZT0R00"))
      (libsource (lib "eagle-import") (part "passives_20904581_RESISTOR0402_RES"))
    )
    (comp (ref "TP8")
      (value "VDDBH")
      (footprint "eagle-import:PAD.03X.03")
      (libsource (lib "eagle-import") (part "TEST-POINT"))
    )
    (comp (ref "TP9")
      (value "VDDP")
      (footprint "eagle-import:PAD.03X.03")
      (libsource (lib "eagle-import") (part "TEST-POINT"))
    )
    (comp (ref "TP10")
      (value "VDDF")
      (footprint "eagle-import:PAD.03X.03")
      (libsource (lib "eagle-import") (part "TEST-POINT"))
    )
    (comp (ref "U1")
      (value "APOLLO4_BLUE_PLUS_SOC_KBR")
      (footprint "eagle-import:APOLLO4_BLUE_SOC_BGA")
      (fields (field (name "MANUFACTURER") "Ambiq") (field (name "MPN") "AMA4B2KP-KBR"))
      (libsource (lib "eagle-import") (part "APOLLO4_BLUE_PLUS_SOC_KBR"))
    )
    (comp (ref "X1")
      (value "ABM12W")
      (footprint "eagle-import:ABM12W")
      (fields
        (field (name "C-LOAD") "6pF")
        (field (name "FREQUENCY") "32 MHz")
        (field (name "MANUFACTURER") "Abracon")
        (field (name "MAX-ESR") "80Ω")
        (field (name "MPN") "ABM12W-32.0000MHZ-6-D1X-T3")
      )
      (libsource (lib "eagle-import") (part "ABM12W"))
    )
    (comp (ref "X3")
      (value "TXC-9HT12")
      (footprint "eagle-import:TXC-9HT12")
      (fields
        (field (name "C-LOAD") "7pF")
        (field (name "FREQUENCY") "32.768 kHz")
        (field (name "MANUFACTURER") "TXC Corp")
        (field (name "MPN") "9HT12-32.768KDZY-T")
      )
      (libsource (lib "eagle-import") (part "TXC-9HT12"))
    )
    (comp (ref "C77")
      (value "1uF")
      (footprint "eagle-import:0201_CAP")
      (fields (field (name "MANUFACTURER") "Murata") (field (name "MPN") "GRM033R61A105ME44D"))
      (libsource (lib "eagle-import") (part "passives_20904581_CAPACITOR0201_CAP"))
    )
    (comp (ref "C78")
      (value "1uF")
      (footprint "eagle-import:0201_CAP")
      (fields (field (name "MANUFACTURER") "Murata") (field (name "MPN") "GRM033R61A105ME44D"))
      (libsource (lib "eagle-import") (part "passives_20904581_CAPACITOR0201_CAP"))
    )
    (comp (ref "D1")
      (value "BICOLOR-SMD")
      (footprint "eagle-import:LED-0606")
      (fields (field (name "MPN") "MCL0606FRD1GR1T"))
      (libsource (lib "eagle-import") (part "BICOLOR-SMD"))
    )
    (comp (ref "D2")
      (value "BICOLOR-SMD")
      (footprint "eagle-import:LED-0606")
      (fields (field (name "MPN") "MCL0606FYW1RD1T"))
      (libsource (lib "eagle-import") (part "BICOLOR-SMD"))
    )
    (comp (ref "J1")
      (value "TC2030-JLINK-NL-2SIDE")
      (footprint "eagle-import:TC2030-IDC-NL-2SIDE")
      (libsource (lib "eagle-import") (part "TC2030-JLINK-NL-2SIDE"))
    )
    (comp (ref "J2")
      (value "TC2030-JLINK-NL-2SIDE")
      (footprint "eagle-import:TC2030-IDC-NL-2SIDE")
      (libsource (lib "eagle-import") (part "TC2030-JLINK-NL-2SIDE"))
    )
    (comp (ref "R2")
      (value "5.1")
      (footprint "eagle-import:0402_RES")
      (fields (field (name "MPN") "RC0402JR-075R1L"))
      (libsource (lib "eagle-import") (part "RESISTOR0402_RES"))
    )
    (comp (ref "R3")
      (value "5.1")
      (footprint "eagle-import:0402_RES")
      (fields (field (name "MPN") "RC0402JR-075R1L"))
      (libsource (lib "eagle-import") (part "RESISTOR0402_RES"))
    )
    (comp (ref "R4")
      (value "15")
      (footprint "eagle-import:0402_RES")
      (fields (field (name "MPN") "RC0402JR-0715RL"))
      (libsource (lib "eagle-import") (part "RESISTOR0402_RES"))
    )
    (comp (ref "R5")
      (value "15")
      (footprint "eagle-import:0402_RES")
      (fields (field (name "MPN") "RC0402JR-0715RL"))
      (libsource (lib "eagle-import") (part "RESISTOR0402_RES"))
    )
    (comp (ref "RZ6")
      (value "0")
      (footprint "eagle-import:0402_RES")
      (fields (field (name "MPN") "RMCF0402ZT0R00"))
      (libsource (lib "eagle-import") (part "passives_20904581_RESISTOR0402_RES"))
    )
    (comp (ref "RZ7")
      (value "0")
      (footprint "eagle-import:0402_RES")
      (fields (field (name "MPN") "RMCF0402ZT0R00"))
      (libsource (lib "eagle-import") (part "passives_20904581_RESISTOR0402_RES"))
    )
    (comp (ref "RZ8")
      (value "0")
      (footprint "eagle-import:0402_RES")
      (fields (field (name "MPN") "RMCF0402ZT0R00"))
      (libsource (lib "eagle-import") (part "passives_20904581_RESISTOR0402_RES"))
    )
    (comp (ref "RZ10")
      (value "0")
      (footprint "eagle-import:0402_RES")
      (fields (field (name "MPN") "RMCF0402ZT0R00"))
      (libsource (lib "eagle-import") (part "passives_20904581_RESISTOR0402_RES"))
    )
    (comp (ref "RZ11")
      (value "0")
      (footprint "eagle-import:0402_RES")
      (fields (field (name "MPN") "RMCF0402ZT0R00"))
      (libsource (lib "eagle-import") (part "passives_20904581_RESISTOR0402_RES"))
    )
    (comp (ref "SJ1")
      (value "JUMPER-SMT_2_NC_TRACE_SILK")
      (footprint "eagle-import:SMT-JUMPER_2_NC_TRACE_SILK")
      (libsource (lib "eagle-import") (part "JUMPER-SMT_2_NC_TRACE_SILK"))
    )
    (comp (ref "VR2")
      (value "TPS7A0218PDQNR")
      (footprint "eagle-import:4-XDFN-EP")
      (libsource (lib "eagle-import") (part "TPS7A0218PDQNR"))
    )
    (comp (ref "A1")
      (value "ACR0301U")
      (footprint "eagle-import:ACR0301U")
      (fields (field (name "MANUFACTURER") "Abracon"))
      (libsource (lib "eagle-import") (part "ACR0301U"))
    )
    (comp (ref "A2")
      (value "ACR0301U")
      (footprint "eagle-import:ACR0301U")
      (fields (field (name "MANUFACTURER") "Abracon"))
      (libsource (lib "eagle-import") (part "ACR0301U"))
    )
    (comp (ref "A3")
      (value "ACR0301U")
      (footprint "eagle-import:ACR0301U")
      (fields (field (name "MANUFACTURER") "Abracon"))
      (libsource (lib "eagle-import") (part "ACR0301U"))
    )
    (comp (ref "C2")
      (value "2pF")
      (footprint "eagle-import:0201_CAP")
      (fields (field (name "MPN") "CBR02C209A5GAC"))
      (libsource (lib "eagle-import") (part "CAPACITOR0201_CAP"))
    )
    (comp (ref "C3")
      (value "3.3pF")
      (footprint "eagle-import:SMD_2012M-0805US-C")
      (fields
        (field (name "EIA") "C0G")
        (field (name "MANUFACTURER") "KYOCERA AVX")
        (field (name "MPN") "600F3R3BT250XT")
      )
      (libsource (lib "eagle-import") (part "C0805US"))
    )
    (comp (ref "C4")
      (value "3.3pF")
      (footprint "eagle-import:SMD_2012M-0805US-C")
      (fields
        (field (name "EIA") "C0G")
        (field (name "MANUFACTURER") "KYOCERA AVX")
        (field (name "MPN") "600F3R3BT250XT")
      )
      (libsource (lib "eagle-import") (part "C0805US"))
    )
    (comp (ref "C11")
      (value "0.1uF")
      (footprint "eagle-import:SMD_3216M-1206US-C")
      (fields (field (name "EIA") "C0G") (field (name "MPN") "GRM31C5C1H104JA01L"))
      (libsource (lib "eagle-import") (part "C1206US"))
    )
    (comp (ref "C12")
      (value "4.7nF")
      (footprint "eagle-import:SMD_1608M-0603US-C")
      (fields
        (field (name "EIA") "C0G")
        (field (name "FEATURES") "Low ESL")
        (field (name "MANUFACTURER") "KEMET")
        (field (name "MPN") "C0603C472J5GAC7867")
      )
      (libsource (lib "eagle-import") (part "C0603US"))
    )
    (comp (ref "C13")
      (value "4.7nF")
      (footprint "eagle-import:SMD_1608M-0603US-C")
      (fields
        (field (name "EIA") "C0G")
        (field (name "FEATURES") "Low ESL")
        (field (name "MANUFACTURER") "KEMET")
        (field (name "MPN") "C0603C472J5GAC7867")
      )
      (libsource (lib "eagle-import") (part "C0603US"))
    )
    (comp (ref "C14")
      (value "4.7nF")
      (footprint "eagle-import:SMD_1608M-0603US-C")
      (fields
        (field (name "EIA") "C0G")
        (field (name "FEATURES") "Low ESL")
        (field (name "MANUFACTURER") "KEMET")
        (field (name "MPN") "C0603C472J5GAC7867")
      )
      (libsource (lib "eagle-import") (part "C0603US"))
    )
    (comp (ref "C22")
      (value "0.1uF")
      (footprint "eagle-import:SMD_1608M-0603US-C")
      (fields (field (name "FEATURES") "Low ESL") (field (name "MPN") "C1608X7R1H104K080AA"))
      (libsource (lib "eagle-import") (part "C0603US"))
    )
    (comp (ref "C23")
      (value "0.1uF")
      (footprint "eagle-import:0402_CAP")
      (fields (field (name "MPN") "CL05A104KP5NNNC"))
      (libsource (lib "eagle-import") (part "passives_20904581_CAPACITOR0402_CAP"))
    )
    (comp (ref "C24")
      (value "0.1uF")
      (footprint "eagle-import:SMD_1608M-0603US-C")
      (fields (field (name "FEATURES") "Low ESL") (field (name "MPN") "C1608X7R1H104K080AA"))
      (libsource (lib "eagle-import") (part "C0603US"))
    )
    (comp (ref "C25")
      (value "0.1uF")
      (footprint "eagle-import:0402_CAP")
      (fields (field (name "MPN") "CL05A104KP5NNNC"))
      (libsource (lib "eagle-import") (part "passives_20904581_CAPACITOR0402_CAP"))
    )
    (comp (ref "C26")
      (value "0.1uF")
      (footprint "eagle-import:0402_CAP")
      (fields (field (name "MPN") "CL05A104KP5NNNC"))
      (libsource (lib "eagle-import") (part "passives_20904581_CAPACITOR0402_CAP"))
    )
    (comp (ref "C33")
      (value "0.1uF")
      (footprint "eagle-import:0402_CAP")
      (fields (field (name "MPN") "CL05A104KP5NNNC"))
      (libsource (lib "eagle-import") (part "passives_20904581_CAPACITOR0402_CAP"))
    )
    (comp (ref "C34")
      (value "0.1uF")
      (footprint "eagle-import:0402_CAP")
      (fields (field (name "MPN") "CL05A104KP5NNNC"))
      (libsource (lib "eagle-import") (part "passives_20904581_CAPACITOR0402_CAP"))
    )
    (comp (ref "C37")
      (value "0.22uF")
      (footprint "eagle-import:SMD_1608M-0603US-C")
      (fields (field (name "FEATURES") "Low ESL") (field (name "MPN") "C1608X7R1H224K080AB"))
      (libsource (lib "eagle-import") (part "C0603US"))
    )
    (comp (ref "C43")
      (value "100pF")
      (footprint "eagle-import:SMD_1005M-0402US-C")
      (fields (field (name "EIA") "C0G") (field (name "MPN") "C0402C101J3GACTU"))
      (libsource (lib "eagle-import") (part "C0402US"))
    )
    (comp (ref "C49")
      (value "4.7uF")
      (footprint "eagle-import:0603_CAP")
      (fields (field (name "MPN") "C1608X7S1A475K080AC"))
      (libsource (lib "eagle-import") (part "passives_20904581_CAPACITOR0603_CAP"))
    )
    (comp (ref "C50")
      (value "4.7uF")
      (footprint "eagle-import:0603_CAP")
      (fields (field (name "MPN") "C1608X7S1A475K080AC"))
      (libsource (lib "eagle-import") (part "passives_20904581_CAPACITOR0603_CAP"))
    )
    (comp (ref "C54")
      (value "10uF")
      (footprint "eagle-import:SMD_1608M-0603US-C")
      (fields (field (name "MPN") "CM105X5R106M25AT"))
      (libsource (lib "eagle-import") (part "C0603US"))
    )
    (comp (ref "C55")
      (value "10uF")
      (footprint "eagle-import:SMD_1608M-0603US-C")
      (fields (field (name "MPN") "CM105X5R106M25AT"))
      (libsource (lib "eagle-import") (part "C0603US"))
    )
    (comp (ref "C90")
      (value "1uF")
      (footprint "eagle-import:0201_CAP")
      (fields (field (name "MANUFACTURER") "Murata") (field (name "MPN") "GRM033R61A105ME44D"))
      (libsource (lib "eagle-import") (part "passives_20904581_CAPACITOR0201_CAP"))
    )
    (comp (ref "C91")
      (value "1uF")
      (footprint "eagle-import:0201_CAP")
      (fields (field (name "MANUFACTURER") "Murata") (field (name "MPN") "GRM033R61A105ME44D"))
      (libsource (lib "eagle-import") (part "passives_20904581_CAPACITOR0201_CAP"))
    )
    (comp (ref "CX1")
      (value "DNP")
      (footprint "eagle-import:0603_CAP")
      (libsource (lib "eagle-import") (part "passives_20904581_CAPACITOR0603_CAP"))
    )
    (comp (ref "CX2")
      (value "DNP")
      (footprint "eagle-import:0603_CAP")
      (libsource (lib "eagle-import") (part "passives_20904581_CAPACITOR0603_CAP"))
    )
    (comp (ref "FB1")
      (value "BLM03PG330SN1D")
      (footprint "eagle-import:0201_FB")
      (fields (field (name "MANUFACTURER") "Murata"))
      (libsource (lib "eagle-import") (part "FERRITE_BEAD0201"))
    )
    (comp (ref "R1")
      (value "49.9-1%")
      (footprint "eagle-import:0201_RES")
      (fields (field (name "MPN") "ERJ-1GNF49R9C"))
      (libsource (lib "eagle-import") (part "passives_20904581_RESISTOR0201_RES"))
    )
    (comp (ref "R24")
      (value "100k")
      (footprint "eagle-import:0402_RES")
      (fields (field (name "MPN") "RT0402BRE07100KL"))
      (libsource (lib "eagle-import") (part "RESISTOR0402_RES"))
    )
    (comp (ref "RX1")
      (value "DNP")
      (footprint "eagle-import:0603-RES")
      (libsource (lib "eagle-import") (part "passives_20904581_RESISTOR0603_RES"))
    )
    (comp (ref "RZ1")
      (value "0")
      (footprint "eagle-import:0603-RES")
      (fields (field (name "MPN") "RMCF0603ZT0R00"))
      (libsource (lib "eagle-import") (part "passives_20904581_RESISTOR0603_RES"))
    )
    (comp (ref "RZ2")
      (value "0")
      (footprint "eagle-import:0603-RES")
      (fields (field (name "MPN") "RMCF0603ZT0R00"))
      (libsource (lib "eagle-import") (part "passives_20904581_RESISTOR0603_RES"))
    )
    (comp (ref "RZ4")
      (value "0")
      (footprint "eagle-import:0402_RES")
      (fields (field (name "MPN") "RMCF0402ZT0R00"))
      (libsource (lib "eagle-import") (part "passives_20904581_RESISTOR0402_RES"))
    )
    (comp (ref "S2")
      (value "SKY13373")
      (footprint "eagle-import:SKY13373")
      (fields (field (name "MANUFACTURER") "Skyworks") (field (name "MPN") "SKY13373-460LF"))
      (libsource (lib "eagle-import") (part "SKY13373"))
    )
    (comp (ref "S3")
      (value "SIP3241XSIP32414")
      (footprint "eagle-import:TDFN2X2X0P6-8")
      (fields (field (name "MANUFACTURER") "Vishay") (field (name "MPN") "SIP32414DNP-T1-GE4"))
      (libsource (lib "eagle-import") (part "SIP3241XSIP32414"))
    )
    (comp (ref "S4")
      (value "MM8030-2610")
      (footprint "eagle-import:MM8030-2610")
      (fields (field (name "MANUFACTURER") "Murata"))
      (libsource (lib "eagle-import") (part "MM8030-2610"))
    )
    (comp (ref "SJ3")
      (value "JUMPER-SMT_3_1-NC_TRACE_SILK")
      (footprint "eagle-import:SMT-JUMPER_3_1-NC_TRACE_SILK")
      (libsource (lib "eagle-import") (part "JUMPER-SMT_3_1-NC_TRACE_SILK"))
    )
    (comp (ref "SJ4")
      (value "JUMPER-SMT_3_1-NC_TRACE_SILK")
      (footprint "eagle-import:SMT-JUMPER_3_1-NC_TRACE_SILK")
      (libsource (lib "eagle-import") (part "JUMPER-SMT_3_1-NC_TRACE_SILK"))
    )
    (comp (ref "TP0")
      (value "TEST-POINT")
      (footprint "eagle-import:PAD.03X.03")
      (libsource (lib "eagle-import") (part "TEST-POINT"))
    )
    (comp (ref "TP1")
      (value "TEST-POINT")
      (footprint "eagle-import:PAD.03X.03")
      (libsource (lib "eagle-import") (part "TEST-POINT"))
    )
    (comp (ref "TP2")
      (value "TEST-POINT")
      (footprint "eagle-import:PAD.03X.03")
      (libsource (lib "eagle-import") (part "TEST-POINT"))
    )
    (comp (ref "TP3")
      (value "TEST-POINT")
      (footprint "eagle-import:PAD.03X.03")
      (libsource (lib "eagle-import") (part "TEST-POINT"))
    )
    (comp (ref "TP4")
      (value "TEST-POINT")
      (footprint "eagle-import:PAD.03X.03")
      (libsource (lib "eagle-import") (part "TEST-POINT"))
    )
    (comp (ref "TP5")
      (value "TEST-POINT")
      (footprint "eagle-import:PAD.03X.03")
      (libsource (lib "eagle-import") (part "TEST-POINT"))
    )
    (comp (ref "TP6")
      (value "TEST-POINT")
      (footprint "eagle-import:PAD.03X.03")
      (libsource (lib "eagle-import") (part "TEST-POINT"))
    )
    (comp (ref "TP7")
      (value "TEST-POINT")
      (footprint "eagle-import:PAD.03X.03")
      (libsource (lib "eagle-import") (part "TEST-POINT"))
    )
    (comp (ref "U2")
      (value "DW3110")
      (footprint "eagle-import:WLCSP52")
      (fields (field (name "MANUFACTURER") "Qorvo"))
      (libsource (lib "eagle-import") (part "DW3110"))
    )
    (comp (ref "U7")
      (value "QM14068")
      (footprint "eagle-import:QM14068")
      (fields (field (name "MANUFACTURER") "Qorvo"))
      (libsource (lib "eagle-import") (part "QM14068"))
    )
    (comp (ref "VR3")
      (value "TPS7A0218PDQNR")
      (footprint "eagle-import:4-XDFN-EP")
      (libsource (lib "eagle-import") (part "TPS7A0218PDQNR"))
    )
    (comp (ref "X4")
      (value "TXC-8Y")
      (footprint "eagle-import:TXC-8Y")
      (fields
        (field (name "FREQ") "38.4 MHz")
        (field (name "MANUFACTURER") "TXC")
        (field (name "MPN") "8Y38472012")
      )
      (libsource (lib "eagle-import") (part "TXC-8Y"))
    )
    (comp (ref "C5")
      (value "4pF")
      (footprint "eagle-import:0201_CAP")
      (fields (field (name "MANUFACTURER") "Murata") (field (name "MPN") "GRM0335C1H4R0BA01D"))
      (libsource (lib "eagle-import") (part "passives_20904581_CAPACITOR0201_CAP"))
    )
    (comp (ref "C6")
      (value "4pF")
      (footprint "eagle-import:0201_CAP")
      (fields (field (name "MANUFACTURER") "Murata") (field (name "MPN") "GRM0335C1H4R0BA01D"))
      (libsource (lib "eagle-import") (part "passives_20904581_CAPACITOR0201_CAP"))
    )
    (comp (ref "C31")
      (value "0.1uF")
      (footprint "eagle-import:0402_CAP")
      (fields (field (name "MPN") "CL05A104KP5NNNC"))
      (libsource (lib "eagle-import") (part "passives_20904581_CAPACITOR0402_CAP"))
    )
    (comp (ref "C32")
      (value "0.1uF")
      (footprint "eagle-import:0402_CAP")
      (fields (field (name "MPN") "CL05A104KP5NNNC"))
      (libsource (lib "eagle-import") (part "passives_20904581_CAPACITOR0402_CAP"))
    )
    (comp (ref "C35")
      (value "0.1uF")
      (footprint "eagle-import:0402_CAP")
      (fields (field (name "MPN") "CL05A104KP5NNNC"))
      (libsource (lib "eagle-import") (part "passives_20904581_CAPACITOR0402_CAP"))
    )
    (comp (ref "C36")
      (value "0.1uF")
      (footprint "eagle-import:0402_CAP")
      (fields (field (name "MPN") "CL05A104KP5NNNC"))
      (libsource (lib "eagle-import") (part "CAPACITOR0402_CAP"))
    )
    (comp (ref "C44")
      (value "1uF")
      (footprint "eagle-import:0402_CAP")
      (fields (field (name "MPN") "GRM155R70J105KA12J"))
      (libsource (lib "eagle-import") (part "CAPACITOR0402_CAP"))
    )
    (comp (ref "D4")
      (value "DIODE0402")
      (footprint "eagle-import:0402_DIODE")
      (fields (field (name "MPN") "CDSQR400B-HF"))
      (libsource (lib "eagle-import") (part "DIODE0402"))
    )
    (comp (ref "LS1")
      (value "PUI_SMT-0440-T-2-R")
      (footprint "eagle-import:SMT-0440-T-2-R")
      (fields (field (name "MPN") "SMT-0440-T-2-R"))
      (libsource (lib "eagle-import") (part "PUI_SMT-0440-T-2-R"))
    )
    (comp (ref "Q2")
      (value "MOSFET-NCHANNELXFDN-3")
      (footprint "eagle-import:XFDFN-3")
      (libsource (lib "eagle-import") (part "MOSFET-NCHANNELXFDN-3"))
    )
    (comp (ref "R12")
      (value "10k")
      (footprint "eagle-import:0402_RES")
      (fields (field (name "MPN") "RC0402JR-0710KL"))
      (libsource (lib "eagle-import") (part "RESISTOR0402_RES"))
    )
    (comp (ref "R16")
      (value "10k")
      (footprint "eagle-import:0402_RES")
      (fields (field (name "MPN") "RC0402JR-0710KL"))
      (libsource (lib "eagle-import") (part "RESISTOR0402_RES"))
    )
    (comp (ref "R20")
      (value "10k")
      (footprint "eagle-import:0402_RES")
      (fields (field (name "MPN") "RC0402JR-0710KL"))
      (libsource (lib "eagle-import") (part "RESISTOR0402_RES"))
    )
    (comp (ref "R25")
      (value "100k")
      (footprint "eagle-import:0402_RES")
      (fields (field (name "MPN") "RT0402BRE07100KL"))
      (libsource (lib "eagle-import") (part "RESISTOR0402_RES"))
    )
    (comp (ref "RX2")
      (value "DNP")
      (footprint "eagle-import:0603-RES")
      (libsource (lib "eagle-import") (part "passives_20904581_RESISTOR0603_RES"))
    )
    (comp (ref "RX5")
      (value "DNP")
      (footprint "eagle-import:0603-RES")
      (libsource (lib "eagle-import") (part "passives_20904581_RESISTOR0603_RES"))
    )
    (comp (ref "RX6")
      (value "DNP")
      (footprint "eagle-import:0603-RES")
      (libsource (lib "eagle-import") (part "passives_20904581_RESISTOR0603_RES"))
    )
    (comp (ref "RX8")
      (value "DNP")
      (footprint "eagle-import:0603-RES")
      (libsource (lib "eagle-import") (part "passives_20904581_RESISTOR0603_RES"))
    )
    (comp (ref "SJ5")
      (value "JUMPER-SMT_3_1-NC_TRACE_SILK")
      (footprint "eagle-import:SMT-JUMPER_3_1-NC_TRACE_SILK")
      (libsource (lib "eagle-import") (part "JUMPER-SMT_3_1-NC_TRACE_SILK"))
    )
    (comp (ref "SJ6")
      (value "JUMPER-SMT_3_1-NC_TRACE_SILK")
      (footprint "eagle-import:SMT-JUMPER_3_1-NC_TRACE_SILK")
      (libsource (lib "eagle-import") (part "JUMPER-SMT_3_1-NC_TRACE_SILK"))
    )
    (comp (ref "SJ7")
      (value "JUMPER-SMT_3_1-NC_TRACE_SILK")
      (footprint "eagle-import:SMT-JUMPER_3_1-NC_TRACE_SILK")
      (libsource (lib "eagle-import") (part "JUMPER-SMT_3_1-NC_TRACE_SILK"))
    )
    (comp (ref "U6")
      (value "BNO086")
      (footprint "eagle-import:LGA28R0P510X4_5P2X3P8X1")
      (fields (field (name "MANUFACTURER") "CEVA Technologies, Inc."))
      (libsource (lib "eagle-import") (part "BNO086"))
    )
    (comp (ref "U8")
      (value "AS5FXXX04SND")
      (footprint "eagle-import:AS5FXXXXXXXX-XXLXN")
      (fields (field (name "MANUFACTURER") "Alliance Memory") (field (name "MPN") "AS5F18G04SND-10LIN"))
      (libsource (lib "eagle-import") (part "AS5FXXX04SND"))
    )
    (comp (ref "X2")
      (value "TXC-9HT12")
      (footprint "eagle-import:TXC-9HT12")
      (fields
        (field (name "C-LOAD") "7pF")
        (field (name "FREQUENCY") "32.768 kHz")
        (field (name "MANUFACTURER") "TXC Corp")
        (field (name "MPN") "9HT12-32.768KDZY-T")
      )
      (libsource (lib "eagle-import") (part "TXC-9HT12"))
    )
  )
  (nets
    (net (code "1") (name "+1V8") (class "Default")
      (node (ref "C26") (pin "1") (pinfunction "1_1") (pintype "bidirectional"))
      (node (ref "C31") (pin "1") (pinfunction "1_1") (pintype "bidirectional"))
      (node (ref "C35") (pin "1") (pinfunction "1_1") (pintype "bidirectional"))
      (node (ref "C46") (pin "1") (pinfunction "1_1") (pintype "bidirectional"))
      (node (ref "C50") (pin "2") (pinfunction "2_2") (pintype "bidirectional"))
      (node (ref "C62") (pin "P$1") (pinfunction "1_P$1") (pintype "bidirectional"))
      (node (ref "C63") (pin "P$1") (pinfunction "1_P$1") (pintype "bidirectional"))
      (node (ref "C64") (pin "P$1") (pinfunction "1_P$1") (pintype "bidirectional"))
      (node (ref "C65") (pin "P$1") (pinfunction "1_P$1") (pintype "bidirectional"))
      (node (ref "C66") (pin "P$1") (pinfunction "1_P$1") (pintype "bidirectional"))
      (node (ref "C67") (pin "P$1") (pinfunction "1_P$1") (pintype "bidirectional"))
      (node (ref "C75") (pin "P$2") (pinfunction "2_P$2") (pintype "bidirectional"))
      (node (ref "C8") (pin "P$2") (pinfunction "2_P$2") (pintype "bidirectional"))
      (node (ref "J1") (pin "1") (pinfunction "VTREF_1") (pintype "bidirectional"))
      (node (ref "J1") (pin "B1") (pinfunction "VTREF_B1") (pintype "bidirectional"))
      (node (ref "J6") (pin "1") (pinfunction "1_1") (pintype "passive"))
      (node (ref "L2") (pin "P$1") (pinfunction "1_P$1") (pintype "bidirectional"))
      (node (ref "R12") (pin "2") (pinfunction "2_2") (pintype "passive"))
      (node (ref "R16") (pin "2") (pinfunction "2_2") (pintype "passive"))
      (node (ref "R20") (pin "2") (pinfunction "2_2") (pintype "passive"))
      (node (ref "R29") (pin "1") (pinfunction "1_1") (pintype "passive"))
      (node (ref "RX2") (pin "2") (pinfunction "2_2") (pintype "passive"))
      (node (ref "RX5") (pin "1") (pinfunction "1_1") (pintype "passive"))
      (node (ref "RX6") (pin "1") (pinfunction "1_1") (pintype "passive"))
      (node (ref "RX8") (pin "2") (pinfunction "2_2") (pintype "passive"))
      (node (ref "S3") (pin "4") (pinfunction "IN_4") (pintype "bidirectional"))
      (node (ref "SJ1") (pin "2") (pinfunction "2_2") (pintype "passive"))
      (node (ref "SJ4") (pin "1") (pinfunction "1_1") (pintype "passive"))
      (node (ref "SJ7") (pin "3") (pinfunction "3_3") (pintype "passive"))
      (node (ref "TP9") (pin "P$1") (pinfunction "TESTPOINT_P$1") (pintype "bidirectional"))
      (node (ref "U1") (pin "B1") (pinfunction "VDDP-IO_PAD_SUP_B1") (pintype "bidirectional"))
      (node (ref "U1") (pin "C4") (pinfunction "VDDA-ANALOG_SUP_C4") (pintype "bidirectional"))
      (node (ref "U1") (pin "E11") (pinfunction "VDDAUDD_E11") (pintype "bidirectional"))
      (node (ref "U1") (pin "G1") (pinfunction "VDDB-BLE_SUPPLY_G1") (pintype "bidirectional"))
      (node (ref "U1") (pin "M10") (pinfunction "VDDH-HV_SUP_M10") (pintype "bidirectional"))
      (node (ref "U1") (pin "M9") (pinfunction "VDDH2-HV_SUP_M9") (pintype "bidirectional"))
      (node (ref "U2") (pin "B13") (pinfunction "VDD1_B13") (pintype "bidirectional"))
      (node (ref "U6") (pin "28") (pinfunction "VDDIO_28") (pintype "input"))
      (node (ref "U8") (pin "8") (pinfunction "VCC_8") (pintype "bidirectional"))
    )
    (net (code "2") (name "+2V5") (class "Default")
      (node (ref "C32") (pin "1") (pinfunction "1_1") (pintype "bidirectional"))
      (node (ref "C34") (pin "1") (pinfunction "1_1") (pintype "bidirectional"))
      (node (ref "C44") (pin "1") (pinfunction "1_1") (pintype "bidirectional"))
      (node (ref "C47") (pin "2") (pinfunction "2_2") (pintype "bidirectional"))
      (node (ref "C49") (pin "1") (pinfunction "1_1") (pintype "bidirectional"))
      (node (ref "C7") (pin "P$1") (pinfunction "1_P$1") (pintype "bidirectional"))
      (node (ref "C77") (pin "P$1") (pinfunction "1_P$1") (pintype "bidirectional"))
      (node (ref "C90") (pin "P$1") (pinfunction "1_P$1") (pintype "bidirectional"))
      (node (ref "D4") (pin "CATHODE") (pinfunction "CATHODE_CATHODE") (pintype "bidirectional"))
      (node (ref "J5") (pin "1") (pinfunction "1_1") (pintype "passive"))
      (node (ref "L1") (pin "P$2") (pinfunction "2_P$2") (pintype "bidirectional"))
      (node (ref "LS1") (pin "+") (pinfunction "P_+") (pintype "passive"))
      (node (ref "R28") (pin "2") (pinfunction "2_2") (pintype "passive"))
      (node (ref "RX1") (pin "1") (pinfunction "1_1") (pintype "passive"))
      (node (ref "RZ10") (pin "1") (pinfunction "1_1") (pintype "passive"))
      (node (ref "S2") (pin "6") (pinfunction "VDD_6") (pintype "power_in"))
      (node (ref "S3") (pin "1") (pinfunction "IN_1") (pintype "bidirectional"))
      (node (ref "U6") (pin "3") (pinfunction "VDD_3") (pintype "input"))
      (node (ref "VR2") (pin "4") (pinfunction "IN_4") (pintype "bidirectional"))
      (node (ref "VR3") (pin "4") (pinfunction "IN_4") (pintype "bidirectional"))
    )
    (net (code "3") (name "9DOF_H_SDA{slash}H_MISO{slash}TX") (class "Default")
      (node (ref "RX5") (pin "2") (pinfunction "2_2") (pintype "passive"))
      (node (ref "SJ5") (pin "1") (pinfunction "1_1") (pintype "passive"))
      (node (ref "SJ6") (pin "2") (pinfunction "2_2") (pintype "passive"))
      (node (ref "U6") (pin "20") (pinfunction "H_SDA/H_MISO/TX_20") (pintype "bidirectional"))
    )
    (net (code "4") (name "9DOF_SA0{slash}H_MOSI") (class "Default")
      (node (ref "SJ5") (pin "2") (pinfunction "2_2") (pintype "passive"))
      (node (ref "SJ6") (pin "1") (pinfunction "1_1") (pintype "passive"))
      (node (ref "U6") (pin "17") (pinfunction "SA0/H_MOSI_17") (pintype "input"))
    )
    (net (code "5") (name "AGND") (class "Default")
      (node (ref "C1") (pin "2") (pinfunction "2_2") (pintype "passive"))
      (node (ref "C93") (pin "P$2") (pinfunction "2_P$2") (pintype "bidirectional"))
      (node (ref "CX5") (pin "2") (pinfunction "2_2") (pintype "passive"))
      (node (ref "U1") (pin "M1") (pinfunction "RFIOM_M1") (pintype "bidirectional"))
      (node (ref "U1") (pin "M3") (pinfunction "RFSUB-RF_SUBSTRATE_GND_M3") (pintype "bidirectional"))
    )
    (net (code "6") (name "ANT1") (class "Default")
      (node (ref "A1") (pin "FEED") (pinfunction "ANTENNA_FEED") (pintype "bidirectional"))
      (node (ref "U7") (pin "2") (pinfunction "LNA_IN_2") (pintype "bidirectional"))
    )
    (net (code "7") (name "AP4_GP06{slash}TT_FLASH_~{HOLD_IO3}") (class "Default")
      (node (ref "U1") (pin "J5") (pinfunction "GPIO6_J5") (pintype "bidirectional"))
      (node (ref "U8") (pin "7") (pinfunction "~{HOLD}/SIO3_7") (pintype "bidirectional"))
    )
    (net (code "8") (name "AP4_GP08{slash}TT_9DOF_H_SCL{slash}SCK{slash}RX") (class "Default")
      (node (ref "RX6") (pin "2") (pinfunction "2_2") (pintype "passive"))
      (node (ref "U1") (pin "H2") (pinfunction "GPIO31_H2") (pintype "bidirectional"))
      (node (ref "U6") (pin "19") (pinfunction "H_SCL/SCK/RX_19") (pintype "bidirectional"))
    )
    (net (code "9") (name "AP4_GP09{slash}TT_9DOF_H_MOSI") (class "Default")
      (node (ref "SJ5") (pin "3") (pinfunction "3_3") (pintype "passive"))
      (node (ref "U1") (pin "G2") (pinfunction "GPIO32_G2") (pintype "bidirectional"))
    )
    (net (code "10") (name "AP4_GP10{slash}TT_9DOF_H_MISO") (class "Default")
      (node (ref "SJ6") (pin "3") (pinfunction "3_3") (pintype "passive"))
      (node (ref "U1") (pin "G3") (pinfunction "GPIO33_G3") (pintype "bidirectional"))
    )
    (net (code "11") (name "AP4_GP13{slash}TT_9DOF_~{BOOT}") (class "Default")
      (node (ref "R20") (pin "1") (pinfunction "1_1") (pintype "passive"))
      (node (ref "U1") (pin "D5") (pinfunction "GPIO13_D5") (pintype "bidirectional"))
      (node (ref "U6") (pin "4") (pinfunction "~{BOOT}_4") (pintype "input"))
    )
    (net (code "12") (name "AP4_GP14{slash}TT_~{DW_SPI_CS}") (class "Default")
      (node (ref "U1") (pin "D6") (pinfunction "GPIO14_D6") (pintype "bidirectional"))
      (node (ref "U2") (pin "B5") (pinfunction "~{SPICS}_B5") (pintype "bidirectional"))
    )
    (net (code "13") (name "AP4_GP17{slash}TT_9DOF_H_~{INT}") (class "Default")
      (node (ref "U1") (pin "D4") (pinfunction "GPIO17_D4") (pintype "bidirectional"))
      (node (ref "U6") (pin "14") (pinfunction "H_INTN_14") (pintype "output"))
    )
    (net (code "14") (name "AP4_GP18{slash}TT_BATIN") (class "Default")
      (node (ref "C27") (pin "1") (pinfunction "1_1") (pintype "bidirectional"))
      (node (ref "R30") (pin "2") (pinfunction "2_2") (pintype "passive"))
      (node (ref "R31") (pin "1") (pinfunction "1_1") (pintype "passive"))
      (node (ref "U1") (pin "D3") (pinfunction "GPIO18_D3") (pintype "bidirectional"))
    )
    (net (code "15") (name "AP4_GP24{slash}TT_RFSW_V1") (class "Default")
      (node (ref "CX2") (pin "1") (pinfunction "1_1") (pintype "bidirectional"))
      (node (ref "S2") (pin "4") (pinfunction "V1_4") (pintype "input"))
      (node (ref "U1") (pin "E2") (pinfunction "GPIO24_E2") (pintype "bidirectional"))
    )
    (net (code "16") (name "AP4_GP25{slash}TT_RFSW_V2") (class "Default")
      (node (ref "CX1") (pin "1") (pinfunction "1_1") (pintype "bidirectional"))
      (node (ref "S2") (pin "5") (pinfunction "V2_5") (pintype "input"))
      (node (ref "U1") (pin "K5") (pinfunction "GPIO25_K5") (pintype "bidirectional"))
    )
    (net (code "17") (name "AP4_GP26{slash}TT_DW_WAKEUP") (class "Default")
      (node (ref "U1") (pin "L5") (pinfunction "GPIO26_L5") (pintype "bidirectional"))
      (node (ref "U2") (pin "B9") (pinfunction "WAKEUP_B9") (pintype "bidirectional"))
    )
    (net (code "18") (name "AP4_GP27{slash}TT_DW_IRQ") (class "Default")
      (node (ref "R24") (pin "2") (pinfunction "2_2") (pintype "passive"))
      (node (ref "U1") (pin "M5") (pinfunction "GPIO27_M5") (pintype "bidirectional"))
      (node (ref "U2") (pin "B1") (pinfunction "IRQ/GPIO8_B1") (pintype "bidirectional"))
    )
    (net (code "19") (name "AP4_GP30{slash}TT_FLASH_~{WP}") (class "Default")
      (node (ref "U1") (pin "G4") (pinfunction "GPIO30_G4") (pintype "bidirectional"))
      (node (ref "U8") (pin "3") (pinfunction "~{WP}/SIO2_3") (pintype "bidirectional"))
    )
    (net (code "20") (name "AP4_GP31{slash}TT_DW_SPI_CLK") (class "Default")
      (node (ref "U1") (pin "E8") (pinfunction "GPIO8_E8") (pintype "bidirectional"))
      (node (ref "U2") (pin "A8") (pinfunction "SPICLK_A8") (pintype "bidirectional"))
    )
    (net (code "21") (name "AP4_GP32{slash}TT_DW_SPI_IO0") (class "Default")
      (node (ref "U1") (pin "E7") (pinfunction "GPIO9_E7") (pintype "bidirectional"))
      (node (ref "U2") (pin "B7") (pinfunction "SPICDI(MOSI)_B7") (pintype "bidirectional"))
    )
    (net (code "22") (name "AP4_GP33{slash}TT_DW_SPI_IO1") (class "Default")
      (node (ref "U1") (pin "E6") (pinfunction "GPIO10_E6") (pintype "bidirectional"))
      (node (ref "U2") (pin "A6") (pinfunction "SPICDO(MISO)_A6") (pintype "bidirectional"))
    )
    (net (code "23") (name "AP4_GP47{slash}TT_FLASH_SCK") (class "Default")
      (node (ref "U1") (pin "F1") (pinfunction "GPIO47_F1") (pintype "bidirectional"))
      (node (ref "U8") (pin "6") (pinfunction "SCLK_6") (pintype "input"))
    )
    (net (code "24") (name "AP4_GP48{slash}TT_FLASH_PDI_IO0") (class "Default")
      (node (ref "U1") (pin "E1") (pinfunction "GPIO48_E1") (pintype "bidirectional"))
      (node (ref "U8") (pin "5") (pinfunction "SI/SIO0_5") (pintype "bidirectional"))
    )
    (net (code "25") (name "AP4_GP49{slash}TT_FLASH_PDO_IO1") (class "Default")
      (node (ref "U1") (pin "D1") (pinfunction "GPIO49_D1") (pintype "bidirectional"))
      (node (ref "U8") (pin "2") (pinfunction "SO/SIO1_2") (pintype "bidirectional"))
    )
    (net (code "26") (name "AP4_GP50{slash}TT_~{DW_RESET}") (class "Default")
      (node (ref "U1") (pin "A9") (pinfunction "GPIO50_A9") (pintype "bidirectional"))
      (node (ref "U2") (pin "A10") (pinfunction "~{RST}_A10") (pintype "bidirectional"))
    )
    (net (code "27") (name "AP4_GP51{slash}LED1_GREEN") (class "Default")
      (node (ref "R2") (pin "2") (pinfunction "2_2") (pintype "passive"))
      (node (ref "U1") (pin "B9") (pinfunction "GPIO51_B9") (pintype "bidirectional"))
    )
    (net (code "28") (name "AP4_GP53{slash}LED1_RED") (class "Default")
      (node (ref "R5") (pin "2") (pinfunction "2_2") (pintype "passive"))
      (node (ref "U1") (pin "C9") (pinfunction "GPIO53_C9") (pintype "bidirectional"))
    )
    (net (code "29") (name "AP4_GP55{slash}TT_BUZZER_GATE") (class "Default")
      (node (ref "Q2") (pin "G") (pinfunction "G_G") (pintype "passive"))
      (node (ref "R25") (pin "1") (pinfunction "1_1") (pintype "passive"))
      (node (ref "U1") (pin "D9") (pinfunction "GPIO55_D9") (pintype "bidirectional"))
    )
    (net (code "30") (name "AP4_GP58{slash}TT_~{CHG}") (class "Default")
      (node (ref "U1") (pin "J7") (pinfunction "GPIO58_J7") (pintype "bidirectional"))
      (node (ref "U3") (pin "8") (pinfunction "~{CHG}_8") (pintype "bidirectional"))
      (node (ref "U4") (pin "7") (pinfunction "~{CHG}_7") (pintype "bidirectional"))
    )
    (net (code "31") (name "AP4_GP60{slash}TT_~{PG}") (class "Default")
      (node (ref "U1") (pin "K8") (pinfunction "GPIO60_K8") (pintype "bidirectional"))
      (node (ref "U3") (pin "5") (pinfunction "~{PG}_5") (pintype "bidirectional"))
    )
    (net (code "32") (name "AP4_GP63{slash}TT_9DOF_PS0{slash}WAKE") (class "Default")
      (node (ref "U1") (pin "M6") (pinfunction "GPIO63_M6") (pintype "bidirectional"))
      (node (ref "U6") (pin "6") (pinfunction "PS0/WAKE_6") (pintype "input"))
    )
    (net (code "33") (name "AP4_GP65{slash}TT_9DOF_~{RESET}") (class "Default")
      (node (ref "RX8") (pin "1") (pinfunction "1_1") (pintype "passive"))
      (node (ref "U1") (pin "A7") (pinfunction "GPIO65_A7") (pintype "bidirectional"))
      (node (ref "U6") (pin "11") (pinfunction "~{RESET}_11") (pintype "input"))
    )
    (net (code "34") (name "AP4_GP66{slash}TT_QI_TS_CTRL") (class "Default")
      (node (ref "C30") (pin "1") (pinfunction "1_1") (pintype "bidirectional"))
      (node (ref "RT1") (pin "2") (pinfunction "2_2") (pintype "passive"))
      (node (ref "U1") (pin "A8") (pinfunction "GPIO66_A8") (pintype "bidirectional"))
      (node (ref "U4") (pin "13") (pinfunction "TS/CTRL_13") (pintype "bidirectional"))
    )
    (net (code "35") (name "AP4_GP69{slash}TT_FLASH_~{CS}") (class "Default")
      (node (ref "RX2") (pin "1") (pinfunction "1_1") (pintype "passive"))
      (node (ref "U1") (pin "B8") (pinfunction "GPIO69_B8") (pintype "bidirectional"))
      (node (ref "U8") (pin "1") (pinfunction "~{CS}_1") (pintype "input"))
    )
    (net (code "36") (name "AP4_GP72{slash}TT_9DOF_H_~{CS}") (class "Default")
      (node (ref "U1") (pin "C8") (pinfunction "GPIO72_C8") (pintype "bidirectional"))
      (node (ref "U6") (pin "18") (pinfunction "H_~{CS}_18") (pintype "input"))
    )
    (net (code "37") (name "AP4_GP79{slash}LED2_RED") (class "Default")
      (node (ref "R4") (pin "2") (pinfunction "2_2") (pintype "passive"))
      (node (ref "U1") (pin "M11") (pinfunction "GPIO79_M11") (pintype "bidirectional"))
    )
    (net (code "38") (name "AP4_GP80{slash}SWTRACE0") (class "Default")
      (node (ref "J2") (pin "2") (pinfunction "SWDIO_2") (pintype "bidirectional"))
      (node (ref "J2") (pin "B2") (pinfunction "SWDIO_B2") (pintype "bidirectional"))
      (node (ref "U1") (pin "K10") (pinfunction "GPIO80_K10") (pintype "bidirectional"))
    )
    (net (code "39") (name "AP4_GP81{slash}SWTRACE1") (class "Default")
      (node (ref "J2") (pin "4") (pinfunction "SWDCLK_4") (pintype "bidirectional"))
      (node (ref "J2") (pin "B4") (pinfunction "SWDCLK_B4") (pintype "bidirectional"))
      (node (ref "U1") (pin "L10") (pinfunction "GPIO81_L10") (pintype "bidirectional"))
    )
    (net (code "40") (name "AP4_GP82{slash}SWTRACE2") (class "Default")
      (node (ref "J2") (pin "6") (pinfunction "SWO_6") (pintype "bidirectional"))
      (node (ref "J2") (pin "B6") (pinfunction "SWO_B6") (pintype "bidirectional"))
      (node (ref "U1") (pin "L9") (pinfunction "GPIO82_L9") (pintype "bidirectional"))
    )
    (net (code "41") (name "AP4_GP83{slash}SWTRACE3") (class "Default")
      (node (ref "J2") (pin "3") (pinfunction "~{RESET}_3") (pintype "bidirectional"))
      (node (ref "J2") (pin "B3") (pinfunction "~{RESET}_B3") (pintype "bidirectional"))
      (node (ref "U1") (pin "K9") (pinfunction "GPIO83_K9") (pintype "bidirectional"))
    )
    (net (code "42") (name "AP4_GP88{slash}LED2_YLW") (class "Default")
      (node (ref "R3") (pin "2") (pinfunction "2_2") (pintype "passive"))
      (node (ref "U1") (pin "F9") (pinfunction "GPIO88_F9") (pintype "bidirectional"))
    )
    (net (code "43") (name "AP4_SWDCLK") (class "Default")
      (node (ref "J1") (pin "4") (pinfunction "SWDCLK_4") (pintype "bidirectional"))
      (node (ref "J1") (pin "B4") (pinfunction "SWDCLK_B4") (pintype "bidirectional"))
      (node (ref "U1") (pin "K3") (pinfunction "GPIO20_K3") (pintype "bidirectional"))
    )
    (net (code "44") (name "AP4_SWDIO") (class "Default")
      (node (ref "J1") (pin "2") (pinfunction "SWDIO_2") (pintype "bidirectional"))
      (node (ref "J1") (pin "B2") (pinfunction "SWDIO_B2") (pintype "bidirectional"))
      (node (ref "U1") (pin "J3") (pinfunction "GPIO21_J3") (pintype "bidirectional"))
    )
    (net (code "45") (name "AP4_SWO") (class "Default")
      (node (ref "J1") (pin "6") (pinfunction "SWO_6") (pintype "bidirectional"))
      (node (ref "J1") (pin "B6") (pinfunction "SWO_B6") (pintype "bidirectional"))
      (node (ref "U1") (pin "L4") (pinfunction "GPIO3_L4") (pintype "bidirectional"))
    )
    (net (code "46") (name "AP4_SWTRACECLK") (class "Default")
      (node (ref "J2") (pin "1") (pinfunction "VTREF_1") (pintype "bidirectional"))
      (node (ref "J2") (pin "B1") (pinfunction "VTREF_B1") (pintype "bidirectional"))
      (node (ref "U1") (pin "F12") (pinfunction "GPIO38_F12") (pintype "bidirectional"))
    )
    (net (code "47") (name "AP4_USB0_N") (class "Default")
      (node (ref "U1") (pin "M8") (pinfunction "USB0PN_M8") (pintype "bidirectional"))
    )
    (net (code "48") (name "AP4_USB0_P") (class "Default")
      (node (ref "U1") (pin "M7") (pinfunction "USB0PP_M7") (pintype "bidirectional"))
    )
    (net (code "49") (name "AP4_VDDBH") (class "Default")
      (node (ref "C69") (pin "1") (pinfunction "1_1") (pintype "bidirectional"))
      (node (ref "L6") (pin "2") (pinfunction "2_2") (pintype "bidirectional"))
      (node (ref "RZ9") (pin "1") (pinfunction "1_1") (pintype "passive"))
      (node (ref "TP8") (pin "P$1") (pinfunction "TESTPOINT_P$1") (pintype "bidirectional"))
      (node (ref "U1") (pin "G12") (pinfunction "VDDBH--BLE_BUCK_VOUT_G12") (pintype "bidirectional"))
    )
    (net (code "50") (name "AP4_VDDBH_RF") (class "Default")
      (node (ref "C93") (pin "P$1") (pinfunction "1_P$1") (pintype "bidirectional"))
      (node (ref "RZ9") (pin "2") (pinfunction "2_2") (pintype "passive"))
      (node (ref "U1") (pin "J1") (pinfunction "VDDBH_RF--BLE_BUCK_RF_VOUT_J1") (pintype "bidirectional"))
    )
    (net (code "51") (name "AP4_VDDF") (class "Default")
      (node (ref "C61") (pin "P$1") (pinfunction "1_P$1") (pintype "bidirectional"))
      (node (ref "C75") (pin "P$1") (pinfunction "1_P$1") (pintype "bidirectional"))
      (node (ref "TP10") (pin "P$1") (pinfunction "TESTPOINT_P$1") (pintype "bidirectional"))
      (node (ref "U1") (pin "C2") (pinfunction "VDDF-MEM_C2") (pintype "bidirectional"))
    )
    (net (code "52") (name "AP4_VDDMIPI_1P8") (class "Default")
      (node (ref "C70") (pin "P$1") (pinfunction "1_P$1") (pintype "bidirectional"))
      (node (ref "RZ8") (pin "1") (pinfunction "1_1") (pintype "passive"))
      (node (ref "U1") (pin "H10") (pinfunction "VDD18-MIPI_H10") (pintype "bidirectional"))
    )
    (net (code "53") (name "AP4_VDDUSB_0P9") (class "Default")
      (node (ref "C73") (pin "P$1") (pinfunction "1_P$1") (pintype "bidirectional"))
      (node (ref "RZ6") (pin "1") (pinfunction "1_1") (pintype "passive"))
      (node (ref "U1") (pin "L7") (pinfunction "VDDUSB0P9_L7") (pintype "bidirectional"))
    )
    (net (code "54") (name "AP4_VDDUSB_3P3") (class "Default")
      (node (ref "C74") (pin "P$1") (pinfunction "1_P$1") (pintype "bidirectional"))
      (node (ref "RZ7") (pin "1") (pinfunction "1_1") (pintype "passive"))
      (node (ref "U1") (pin "K7") (pinfunction "VDDUSB33_K7") (pintype "bidirectional"))
    )
    (net (code "55") (name "AP4_~{RESET}") (class "Default")
      (node (ref "C76") (pin "1") (pinfunction "1_1") (pintype "passive"))
      (node (ref "D3") (pin "1") (pinfunction "C_1") (pintype "passive"))
      (node (ref "J1") (pin "3") (pinfunction "~{RESET}_3") (pintype "bidirectional"))
      (node (ref "J1") (pin "B3") (pinfunction "~{RESET}_B3") (pintype "bidirectional"))
      (node (ref "U1") (pin "A6") (pinfunction "~{RST}_A6") (pintype "input"))
    )
    (net (code "56") (name "BATT_THERM") (class "Default")
      (node (ref "J4") (pin "2") (pinfunction "2_2") (pintype "bidirectional"))
      (node (ref "J4") (pin "2SUPP") (pinfunction "2_2SUPP") (pintype "bidirectional"))
      (node (ref "SJ2") (pin "3") (pinfunction "3_3") (pintype "passive"))
    )
    (net (code "57") (name "BATT_TS") (class "Default")
      (node (ref "SJ2") (pin "2") (pinfunction "2_2") (pintype "passive"))
      (node (ref "U3") (pin "9") (pinfunction "TS_9") (pintype "bidirectional"))
    )
    (net (code "58") (name "BNO_ENV_SCL") (class "Default")
      (node (ref "R12") (pin "1") (pinfunction "1_1") (pintype "passive"))
      (node (ref "U6") (pin "15") (pinfunction "ENV_SCL_15") (pintype "bidirectional"))
    )
    (net (code "59") (name "BNO_ENV_SDA") (class "Default")
      (node (ref "R16") (pin "1") (pinfunction "1_1") (pintype "passive"))
      (node (ref "U6") (pin "16") (pinfunction "ENV_SDA_16") (pintype "bidirectional"))
    )
    (net (code "60") (name "D+") (class "Default")
      (node (ref "XJ1") (pin "A6") (pinfunction "DP1_A6") (pintype "bidirectional"))
      (node (ref "XJ1") (pin "B6") (pinfunction "DP2_B6") (pintype "bidirectional"))
    )
    (net (code "61") (name "D-") (class "Default")
      (node (ref "XJ1") (pin "A7") (pinfunction "DN1_A7") (pintype "bidirectional"))
      (node (ref "XJ1") (pin "B7") (pinfunction "DN2_B7") (pintype "bidirectional"))
    )
    (net (code "62") (name "DW_EXTON") (class "Default")
      (node (ref "RX1") (pin "2") (pinfunction "2_2") (pintype "passive"))
      (node (ref "S3") (pin "2") (pinfunction "CTL_2") (pintype "bidirectional"))
      (node (ref "S3") (pin "3") (pinfunction "CTL_3") (pintype "bidirectional"))
      (node (ref "SJ4") (pin "2") (pinfunction "2_2") (pintype "passive"))
      (node (ref "VR3") (pin "3") (pinfunction "EN_3") (pintype "input"))
    )
    (net (code "63") (name "DW_EXTON_RAW") (class "Default")
      (node (ref "SJ4") (pin "3") (pinfunction "3_3") (pintype "passive"))
      (node (ref "U2") (pin "A12") (pinfunction "EXTON_A12") (pintype "bidirectional"))
    )
    (net (code "64") (name "DW_GPIO6{slash}EXTRXE") (class "Default")
      (node (ref "SJ3") (pin "3") (pinfunction "3_3") (pintype "passive"))
      (node (ref "TP6") (pin "P$1") (pinfunction "TESTPOINT_P$1") (pintype "bidirectional"))
      (node (ref "U2") (pin "C4") (pinfunction "GPIO6/EXTRXE/SPIPHA_C4") (pintype "bidirectional"))
    )
    (net (code "65") (name "DW_SYNC") (class "Default")
      (node (ref "TP7") (pin "P$1") (pinfunction "TESTPOINT_P$1") (pintype "bidirectional"))
      (node (ref "U2") (pin "G2") (pinfunction "GPIO7/SYNC_G2") (pintype "bidirectional"))
    )
    (net (code "66") (name "DW_VDD2_SUP") (class "Default")
      (node (ref "C13") (pin "P$1") (pinfunction "P$1_P$1") (pintype "bidirectional"))
      (node (ref "C24") (pin "P$1") (pinfunction "P$1_P$1") (pintype "bidirectional"))
      (node (ref "C55") (pin "P$1") (pinfunction "P$1_P$1") (pintype "bidirectional"))
      (node (ref "FB1") (pin "P$1") (pinfunction "P$1_P$1") (pintype "bidirectional"))
      (node (ref "RZ1") (pin "2") (pinfunction "2_2") (pintype "passive"))
      (node (ref "U2") (pin "B15") (pinfunction "VDD2B_B15") (pintype "bidirectional"))
    )
    (net (code "67") (name "DW_VDD3_SUP") (class "Default")
      (node (ref "C14") (pin "P$2") (pinfunction "P$2_P$2") (pintype "bidirectional"))
      (node (ref "C22") (pin "P$2") (pinfunction "P$2_P$2") (pintype "bidirectional"))
      (node (ref "C54") (pin "P$2") (pinfunction "P$2_P$2") (pintype "bidirectional"))
      (node (ref "RZ2") (pin "2") (pinfunction "2_2") (pintype "passive"))
      (node (ref "U2") (pin "D15") (pinfunction "VDD3_D15") (pintype "bidirectional"))
    )
    (net (code "68") (name "GND") (class "Default")
      (node (ref "C11") (pin "P$2") (pinfunction "P$2_P$2") (pintype "bidirectional"))
      (node (ref "C12") (pin "P$2") (pinfunction "P$2_P$2") (pintype "bidirectional"))
      (node (ref "C13") (pin "P$2") (pinfunction "P$2_P$2") (pintype "bidirectional"))
      (node (ref "C14") (pin "P$1") (pinfunction "P$1_P$1") (pintype "bidirectional"))
      (node (ref "C22") (pin "P$1") (pinfunction "P$1_P$1") (pintype "bidirectional"))
      (node (ref "C23") (pin "2") (pinfunction "2_2") (pintype "bidirectional"))
      (node (ref "C24") (pin "P$2") (pinfunction "P$2_P$2") (pintype "bidirectional"))
      (node (ref "C25") (pin "2") (pinfunction "2_2") (pintype "bidirectional"))
      (node (ref "C26") (pin "2") (pinfunction "2_2") (pintype "bidirectional"))
      (node (ref "C27") (pin "2") (pinfunction "2_2") (pintype "bidirectional"))
      (node (ref "C28") (pin "2") (pinfunction "2_2") (pintype "bidirectional"))
      (node (ref "C29") (pin "2") (pinfunction "2_2") (pintype "bidirectional"))
      (node (ref "C3") (pin "P$2") (pinfunction "P$2_P$2") (pintype "bidirectional"))
      (node (ref "C30") (pin "2") (pinfunction "2_2") (pintype "bidirectional"))
      (node (ref "C31") (pin "2") (pinfunction "2_2") (pintype "bidirectional"))
      (node (ref "C32") (pin "2") (pinfunction "2_2") (pintype "bidirectional"))
      (node (ref "C33") (pin "2") (pinfunction "2_2") (pintype "bidirectional"))
      (node (ref "C34") (pin "2") (pinfunction "2_2") (pintype "bidirectional"))
      (node (ref "C35") (pin "2") (pinfunction "2_2") (pintype "bidirectional"))
      (node (ref "C36") (pin "2") (pinfunction "2_2") (pintype "bidirectional"))
      (node (ref "C37") (pin "P$1") (pinfunction "P$1_P$1") (pintype "bidirectional"))
      (node (ref "C4") (pin "P$2") (pinfunction "P$2_P$2") (pintype "bidirectional"))
      (node (ref "C40") (pin "1") (pinfunction "1_1") (pintype "bidirectional"))
      (node (ref "C41") (pin "2") (pinfunction "2_2") (pintype "bidirectional"))
      (node (ref "C42") (pin "2") (pinfunction "2_2") (pintype "bidirectional"))
      (node (ref "C43") (pin "P$2") (pinfunction "P$2_P$2") (pintype "bidirectional"))
      (node (ref "C44") (pin "2") (pinfunction "2_2") (pintype "bidirectional"))
      (node (ref "C45") (pin "1") (pinfunction "1_1") (pintype "bidirectional"))
      (node (ref "C46") (pin "2") (pinfunction "2_2") (pintype "bidirectional"))
      (node (ref "C47") (pin "1") (pinfunction "1_1") (pintype "bidirectional"))
      (node (ref "C48") (pin "2") (pinfunction "2_2") (pintype "bidirectional"))
      (node (ref "C49") (pin "2") (pinfunction "2_2") (pintype "bidirectional"))
      (node (ref "C5") (pin "P$1") (pinfunction "1_P$1") (pintype "bidirectional"))
      (node (ref "C50") (pin "1") (pinfunction "1_1") (pintype "bidirectional"))
      (node (ref "C53") (pin "2") (pinfunction "2_2") (pintype "bidirectional"))
      (node (ref "C54") (pin "P$1") (pinfunction "P$1_P$1") (pintype "bidirectional"))
      (node (ref "C55") (pin "P$2") (pinfunction "P$2_P$2") (pintype "bidirectional"))
      (node (ref "C56") (pin "2") (pinfunction "2_2") (pintype "bidirectional"))
      (node (ref "C57") (pin "2") (pinfunction "2_2") (pintype "bidirectional"))
      (node (ref "C58") (pin "P$2") (pinfunction "2_P$2") (pintype "bidirectional"))
      (node (ref "C59") (pin "P$2") (pinfunction "2_P$2") (pintype "bidirectional"))
      (node (ref "C6") (pin "P$1") (pinfunction "1_P$1") (pintype "bidirectional"))
      (node (ref "C60") (pin "P$2") (pinfunction "2_P$2") (pintype "bidirectional"))
      (node (ref "C61") (pin "P$2") (pinfunction "2_P$2") (pintype "bidirectional"))
      (node (ref "C62") (pin "P$2") (pinfunction "2_P$2") (pintype "bidirectional"))
      (node (ref "C63") (pin "P$2") (pinfunction "2_P$2") (pintype "bidirectional"))
      (node (ref "C64") (pin "P$2") (pinfunction "2_P$2") (pintype "bidirectional"))
      (node (ref "C65") (pin "P$2") (pinfunction "2_P$2") (pintype "bidirectional"))
      (node (ref "C66") (pin "P$2") (pinfunction "2_P$2") (pintype "bidirectional"))
      (node (ref "C67") (pin "P$2") (pinfunction "2_P$2") (pintype "bidirectional"))
      (node (ref "C69") (pin "2") (pinfunction "2_2") (pintype "bidirectional"))
      (node (ref "C70") (pin "P$2") (pinfunction "2_P$2") (pintype "bidirectional"))
      (node (ref "C71") (pin "P$1") (pinfunction "1_P$1") (pintype "bidirectional"))
      (node (ref "C72") (pin "P$2") (pinfunction "2_P$2") (pintype "bidirectional"))
      (node (ref "C73") (pin "P$2") (pinfunction "2_P$2") (pintype "bidirectional"))
      (node (ref "C74") (pin "P$2") (pinfunction "2_P$2") (pintype "bidirectional"))
      (node (ref "C76") (pin "2") (pinfunction "2_2") (pintype "passive"))
      (node (ref "C77") (pin "P$2") (pinfunction "2_P$2") (pintype "bidirectional"))
      (node (ref "C78") (pin "P$2") (pinfunction "2_P$2") (pintype "bidirectional"))
      (node (ref "C79") (pin "P$1") (pinfunction "1_P$1") (pintype "bidirectional"))
      (node (ref "C80") (pin "2") (pinfunction "2_2") (pintype "passive"))
      (node (ref "C81") (pin "2") (pinfunction "2_2") (pintype "passive"))
      (node (ref "C90") (pin "P$2") (pinfunction "2_P$2") (pintype "bidirectional"))
      (node (ref "C91") (pin "P$2") (pinfunction "2_P$2") (pintype "bidirectional"))
      (node (ref "CX1") (pin "2") (pinfunction "2_2") (pintype "bidirectional"))
      (node (ref "CX2") (pin "2") (pinfunction "2_2") (pintype "bidirectional"))
      (node (ref "CX3") (pin "2") (pinfunction "2_2") (pintype "passive"))
      (node (ref "CX4") (pin "2") (pinfunction "2_2") (pintype "passive"))
      (node (ref "D3") (pin "2") (pinfunction "A_2") (pintype "passive"))
      (node (ref "J1") (pin "5") (pinfunction "GND_5") (pintype "bidirectional"))
      (node (ref "J1") (pin "B5") (pinfunction "GND_B5") (pintype "bidirectional"))
      (node (ref "J2") (pin "5") (pinfunction "GND_5") (pintype "bidirectional"))
      (node (ref "J2") (pin "B5") (pinfunction "GND_B5") (pintype "bidirectional"))
      (node (ref "J3") (pin "2") (pinfunction "2_2") (pintype "passive"))
      (node (ref "J4") (pin "1") (pinfunction "1_1") (pintype "bidirectional"))
      (node (ref "J4") (pin "1SUPP") (pinfunction "1_1SUPP") (pintype "bidirectional"))
      (node (ref "Q2") (pin "S") (pinfunction "S_S") (pintype "passive"))
      (node (ref "R1") (pin "2") (pinfunction "2_2") (pintype "passive"))
      (node (ref "R15") (pin "1") (pinfunction "1_1") (pintype "passive"))
      (node (ref "R24") (pin "1") (pinfunction "1_1") (pintype "passive"))
      (node (ref "R25") (pin "2") (pinfunction "2_2") (pintype "passive"))
      (node (ref "R26") (pin "1") (pinfunction "1_1") (pintype "passive"))
      (node (ref "R27") (pin "1") (pinfunction "1_1") (pintype "passive"))
      (node (ref "R30") (pin "1") (pinfunction "1_1") (pintype "passive"))
      (node (ref "R6") (pin "2") (pinfunction "2_2") (pintype "passive"))
      (node (ref "RX14") (pin "1") (pinfunction "1_1") (pintype "passive"))
      (node (ref "RX7") (pin "1") (pinfunction "1_1") (pintype "passive"))
      (node (ref "RZ6") (pin "2") (pinfunction "2_2") (pintype "passive"))
      (node (ref "RZ7") (pin "2") (pinfunction "2_2") (pintype "passive"))
      (node (ref "RZ8") (pin "2") (pinfunction "2_2") (pintype "passive"))
      (node (ref "S2") (pin "10") (pinfunction "GND_10") (pintype "bidirectional"))
      (node (ref "S2") (pin "12") (pinfunction "GND_12") (pintype "bidirectional"))
      (node (ref "S2") (pin "2") (pinfunction "GND_2") (pintype "bidirectional"))
      (node (ref "S2") (pin "7") (pinfunction "GND_7") (pintype "bidirectional"))
      (node (ref "S2") (pin "8") (pinfunction "GND_8") (pintype "bidirectional"))
      (node (ref "S2") (pin "PAD") (pinfunction "GND_PAD") (pintype "bidirectional"))
      (node (ref "S3") (pin "6") (pinfunction "GND_6") (pintype "bidirectional"))
      (node (ref "S3") (pin "7") (pinfunction "GND_7") (pintype "bidirectional"))
      (node (ref "S3") (pin "PAD") (pinfunction "GND_PAD") (pintype "bidirectional"))
      (node (ref "S4") (pin "G1") (pinfunction "GND_G1") (pintype "bidirectional"))
      (node (ref "S4") (pin "G2") (pinfunction "GND_G2") (pintype "bidirectional"))
      (node (ref "SJ3") (pin "1") (pinfunction "1_1") (pintype "passive"))
      (node (ref "SJ7") (pin "1") (pinfunction "1_1") (pintype "passive"))
      (node (ref "U1") (pin "B12") (pinfunction "VSSAUDA_B12") (pintype "bidirectional"))
      (node (ref "U1") (pin "B2") (pinfunction "VSSP-BUCK_REGS_GND_B2") (pintype "bidirectional"))
      (node (ref "U1") (pin "B5") (pinfunction "VSSA-ANALOG_GND_B5") (pintype "bidirectional"))
      (node (ref "U1") (pin "D2") (pinfunction "VSS-DGND_FOR_VDDF_AND_PADS_D2") (pintype "bidirectional"))
      (node (ref "U1") (pin "E12") (pinfunction "VSSAUDD_E12") (pintype "bidirectional"))
      (node (ref "U1") (pin "H1") (pinfunction "VSSB-BLE_UNREG_GND_H1") (pintype "bidirectional"))
      (node (ref "U1") (pin "J10") (pinfunction "VSS18-MIPI_J10") (pintype "bidirectional"))
      (node (ref "U1") (pin "L1") (pinfunction "VSSVCO-BLECORE_GND_FOR_VCO_L1") (pintype "bidirectional"))
      (node (ref "U1") (pin "L2") (pinfunction "VSSS-HVSIMOBUCK_GND_L2") (pintype "bidirectional"))
      (node (ref "U1") (pin "L8") (pinfunction "VSSAUSB_L8") (pintype "bidirectional"))
      (node (ref "U2") (pin "A14") (pinfunction "VSS1_A14") (pintype "bidirectional"))
      (node (ref "U2") (pin "A2") (pinfunction "VSS_A2") (pintype "bidirectional"))
      (node (ref "U2") (pin "B11") (pinfunction "VSS1_B11") (pintype "bidirectional"))
      (node (ref "U2") (pin "B3") (pinfunction "VSS_B3") (pintype "bidirectional"))
      (node (ref "U2") (pin "C10") (pinfunction "VSS1_C10") (pintype "bidirectional"))
      (node (ref "U2") (pin "C12") (pinfunction "VSS3_C12") (pintype "bidirectional"))
      (node (ref "U2") (pin "C6") (pinfunction "VSS_C6") (pintype "bidirectional"))
      (node (ref "U2") (pin "C8") (pinfunction "VSS1_C8") (pintype "bidirectional"))
      (node (ref "U2") (pin "D11") (pinfunction "VSS2_D11") (pintype "bidirectional"))
      (node (ref "U2") (pin "D13") (pinfunction "VSS3_D13") (pintype "bidirectional"))
      (node (ref "U2") (pin "D5") (pinfunction "VSS_D5") (pintype "bidirectional"))
      (node (ref "U2") (pin "D7") (pinfunction "VSS_D7") (pintype "bidirectional"))
      (node (ref "U2") (pin "D9") (pinfunction "VSS1_D9") (pintype "bidirectional"))
      (node (ref "U2") (pin "E10") (pinfunction "GND-RF_E10") (pintype "bidirectional"))
      (node (ref "U2") (pin "E12") (pinfunction "GND-RF_E12") (pintype "bidirectional"))
      (node (ref "U2") (pin "E14") (pinfunction "VSS2_E14") (pintype "bidirectional"))
      (node (ref "U2") (pin "E6") (pinfunction "GND-RF_E6") (pintype "bidirectional"))
      (node (ref "U2") (pin "F7") (pinfunction "GND-RF_F7") (pintype "bidirectional"))
      (node (ref "U2") (pin "F9") (pinfunction "GND-RF_F9") (pintype "bidirectional"))
      (node (ref "U2") (pin "G10") (pinfunction "GND-RF_G10") (pintype "bidirectional"))
      (node (ref "U2") (pin "G6") (pinfunction "GND-RF_G6") (pintype "bidirectional"))
      (node (ref "U2") (pin "H1") (pinfunction "GND-RF_H1") (pintype "bidirectional"))
      (node (ref "U2") (pin "H13") (pinfunction "GND-RF_H13") (pintype "bidirectional"))
      (node (ref "U2") (pin "H3") (pinfunction "GND-RF_H3") (pintype "bidirectional"))
      (node (ref "U2") (pin "H7") (pinfunction "GND-RF_H7") (pintype "bidirectional"))
      (node (ref "U2") (pin "H9") (pinfunction "GND-RF_H9") (pintype "bidirectional"))
      (node (ref "U3") (pin "3") (pinfunction "VSS_3") (pintype "bidirectional"))
      (node (ref "U3") (pin "7") (pinfunction "ISET2_7") (pintype "bidirectional"))
      (node (ref "U3") (pin "PAD") (pinfunction "VSS_PAD") (pintype "bidirectional"))
      (node (ref "U4") (pin "1") (pinfunction "PGND_1") (pintype "bidirectional"))
      (node (ref "U4") (pin "10") (pinfunction "EN1_10") (pintype "bidirectional"))
      (node (ref "U4") (pin "11") (pinfunction "EN2_11") (pintype "bidirectional"))
      (node (ref "U4") (pin "20") (pinfunction "PGND_20") (pintype "bidirectional"))
      (node (ref "U4") (pin "PAD") (pinfunction "PGND_PAD") (pintype "bidirectional"))
      (node (ref "U6") (pin "10") (pinfunction "CLKSEL0_10") (pintype "output"))
      (node (ref "U6") (pin "2") (pinfunction "GND_2") (pintype "bidirectional"))
      (node (ref "U6") (pin "25") (pinfunction "GNDIO_25") (pintype "bidirectional"))
      (node (ref "U7") (pin "3") (pinfunction "GND_3") (pintype "bidirectional"))
      (node (ref "U7") (pin "4") (pinfunction "GND_4") (pintype "bidirectional"))
      (node (ref "U7") (pin "5") (pinfunction "GND_5") (pintype "bidirectional"))
      (node (ref "U7") (pin "7") (pinfunction "GND_7") (pintype "bidirectional"))
      (node (ref "U7") (pin "9") (pinfunction "GND_9") (pintype "bidirectional"))
      (node (ref "U8") (pin "4") (pinfunction "GND_4") (pintype "bidirectional"))
      (node (ref "VR1") (pin "13") (pinfunction "GND2_13") (pintype "bidirectional"))
      (node (ref "VR1") (pin "3") (pinfunction "GND2_3") (pintype "bidirectional"))
      (node (ref "VR1") (pin "9") (pinfunction "GND1_9") (pintype "bidirectional"))
      (node (ref "VR2") (pin "2") (pinfunction "GND_2") (pintype "bidirectional"))
      (node (ref "VR2") (pin "PAD") (pinfunction "GND_PAD") (pintype "bidirectional"))
      (node (ref "VR3") (pin "2") (pinfunction "GND_2") (pintype "bidirectional"))
      (node (ref "VR3") (pin "PAD") (pinfunction "GND_PAD") (pintype "bidirectional"))
      (node (ref "X1") (pin "2") (pinfunction "GND_2") (pintype "bidirectional"))
      (node (ref "X1") (pin "4") (pinfunction "GND_4") (pintype "bidirectional"))
      (node (ref "X4") (pin "2") (pinfunction "GND_2") (pintype "bidirectional"))
      (node (ref "X4") (pin "4") (pinfunction "GND_4") (pintype "bidirectional"))
      (node (ref "XJ1") (pin "A1/B12") (pinfunction "GND_A1/B12") (pintype "power_in"))
      (node (ref "XJ1") (pin "B1/A12") (pinfunction "GND_B1/A12") (pintype "power_in"))
      (node (ref "XJ1") (pin "S1") (pinfunction "GND_S1") (pintype "power_in"))
      (node (ref "XJ1") (pin "S2") (pinfunction "GND_S2") (pintype "power_in"))
      (node (ref "XJ1") (pin "S3") (pinfunction "GND_S3") (pintype "power_in"))
      (node (ref "XJ1") (pin "S4") (pinfunction "GND_S4") (pintype "power_in"))
      (node (ref "XR16") (pin "2") (pinfunction "2_2") (pintype "passive"))
      (node (ref "XR17") (pin "2") (pinfunction "2_2") (pintype "passive"))
      (node (ref "XR19") (pin "1") (pinfunction "1_1") (pintype "passive"))
    )
    (net (code "69") (name "Net-(A4-ANTENNA)") (class "Default")
      (node (ref "A4") (pin "S1") (pinfunction "ANTENNA_S1") (pintype "bidirectional"))
      (node (ref "L8") (pin "2") (pinfunction "2_2") (pintype "passive"))
    )
    (net (code "70") (name "Net-(C1-Pad1)") (class "Default")
      (node (ref "C1") (pin "1") (pinfunction "1_1") (pintype "passive"))
      (node (ref "L7") (pin "2") (pinfunction "2_2") (pintype "passive"))
      (node (ref "L8") (pin "1") (pinfunction "1_1") (pintype "passive"))
    )
    (net (code "71") (name "Net-(C2-1)") (class "Default")
      (node (ref "C2") (pin "P$1") (pinfunction "1_P$1") (pintype "bidirectional"))
      (node (ref "U2") (pin "H11") (pinfunction "RF1_H11") (pintype "bidirectional"))
    )
    (net (code "72") (name "Net-(C2-2)") (class "Default")
      (node (ref "C2") (pin "P$2") (pinfunction "2_P$2") (pintype "bidirectional"))
      (node (ref "S2") (pin "11") (pinfunction "RFC_11") (pintype "bidirectional"))
    )
    (net (code "73") (name "Net-(C5-2)") (class "Default")
      (node (ref "C5") (pin "P$2") (pinfunction "2_P$2") (pintype "bidirectional"))
      (node (ref "U6") (pin "27") (pinfunction "XIN32_27") (pintype "bidirectional"))
      (node (ref "X2") (pin "2") (pinfunction "2_2") (pintype "bidirectional"))
    )
    (net (code "74") (name "Net-(C6-2)") (class "Default")
      (node (ref "C6") (pin "P$2") (pinfunction "2_P$2") (pintype "bidirectional"))
      (node (ref "U6") (pin "26") (pinfunction "XOUT32/CLKSEL1_26") (pintype "bidirectional"))
      (node (ref "X2") (pin "1") (pinfunction "1_1") (pintype "bidirectional"))
    )
    (net (code "75") (name "Net-(C7-2)") (class "Default")
      (node (ref "C7") (pin "P$2") (pinfunction "2_P$2") (pintype "bidirectional"))
      (node (ref "R26") (pin "2") (pinfunction "2_2") (pintype "passive"))
      (node (ref "R28") (pin "1") (pinfunction "1_1") (pintype "passive"))
      (node (ref "VR1") (pin "10") (pinfunction "FB2_10") (pintype "bidirectional"))
    )
    (net (code "76") (name "Net-(C8-1)") (class "Default")
      (node (ref "C8") (pin "P$1") (pinfunction "1_P$1") (pintype "bidirectional"))
      (node (ref "R27") (pin "2") (pinfunction "2_2") (pintype "passive"))
      (node (ref "R29") (pin "2") (pinfunction "2_2") (pintype "passive"))
      (node (ref "VR1") (pin "4") (pinfunction "FB1_4") (pintype "bidirectional"))
    )
    (net (code "77") (name "Net-(C58-1)") (class "Default")
      (node (ref "C58") (pin "P$1") (pinfunction "1_P$1") (pintype "bidirectional"))
      (node (ref "U1") (pin "C1") (pinfunction "VDDS-SRAM_HV_SUP_C1") (pintype "bidirectional"))
    )
    (net (code "78") (name "Net-(C59-1)") (class "Default")
      (node (ref "C59") (pin "P$1") (pinfunction "1_P$1") (pintype "bidirectional"))
      (node (ref "U1") (pin "A3") (pinfunction "VDDC-CORE_A3") (pintype "bidirectional"))
    )
    (net (code "79") (name "Net-(C60-1)") (class "Default")
      (node (ref "C60") (pin "P$1") (pinfunction "1_P$1") (pintype "bidirectional"))
      (node (ref "U1") (pin "B3") (pinfunction "VDDC_LV-CORE_LV_B3") (pintype "bidirectional"))
    )
    (net (code "80") (name "Net-(C71-2)") (class "Default")
      (node (ref "C71") (pin "P$2") (pinfunction "2_P$2") (pintype "bidirectional"))
      (node (ref "U1") (pin "B10") (pinfunction "LPMICBIAS_B10") (pintype "output"))
    )
    (net (code "81") (name "Net-(C78-1)") (class "Default")
      (node (ref "C78") (pin "P$1") (pinfunction "1_P$1") (pintype "bidirectional"))
      (node (ref "RZ11") (pin "1") (pinfunction "1_1") (pintype "passive"))
      (node (ref "VR2") (pin "1") (pinfunction "OUT_1") (pintype "power_in"))
    )
    (net (code "82") (name "Net-(C79-2)") (class "Default")
      (node (ref "C79") (pin "P$2") (pinfunction "2_P$2") (pintype "bidirectional"))
      (node (ref "U1") (pin "A12") (pinfunction "LPADC_VREF_A12") (pintype "bidirectional"))
    )
    (net (code "83") (name "Net-(C91-1)") (class "Default")
      (node (ref "C91") (pin "P$1") (pinfunction "1_P$1") (pintype "bidirectional"))
      (node (ref "RZ4") (pin "1") (pinfunction "1_1") (pintype "passive"))
      (node (ref "VR3") (pin "1") (pinfunction "OUT_1") (pintype "power_in"))
    )
    (net (code "84") (name "Net-(D1-PadA1)") (class "Default")
      (node (ref "D1") (pin "A1") (pinfunction "A1_A1") (pintype "bidirectional"))
      (node (ref "D1") (pin "A2") (pinfunction "A2_A2") (pintype "bidirectional"))
      (node (ref "D2") (pin "A1") (pinfunction "A1_A1") (pintype "bidirectional"))
      (node (ref "D2") (pin "A2") (pinfunction "A2_A2") (pintype "bidirectional"))
      (node (ref "SJ1") (pin "1") (pinfunction "1_1") (pintype "passive"))
    )
    (net (code "85") (name "Net-(D1-PadC1)") (class "Default")
      (node (ref "D1") (pin "C1") (pinfunction "C1_C1") (pintype "bidirectional"))
      (node (ref "R5") (pin "1") (pinfunction "1_1") (pintype "passive"))
    )
    (net (code "86") (name "Net-(D1-PadC2)") (class "Default")
      (node (ref "D1") (pin "C2") (pinfunction "C2_C2") (pintype "bidirectional"))
      (node (ref "R2") (pin "1") (pinfunction "1_1") (pintype "passive"))
    )
    (net (code "87") (name "Net-(D2-PadC1)") (class "Default")
      (node (ref "D2") (pin "C1") (pinfunction "C1_C1") (pintype "bidirectional"))
      (node (ref "R4") (pin "1") (pinfunction "1_1") (pintype "passive"))
    )
    (net (code "88") (name "Net-(D2-PadC2)") (class "Default")
      (node (ref "D2") (pin "C2") (pinfunction "C2_C2") (pintype "bidirectional"))
      (node (ref "R3") (pin "1") (pinfunction "1_1") (pintype "passive"))
    )
    (net (code "89") (name "Net-(L1-1)") (class "Default")
      (node (ref "L1") (pin "P$1") (pinfunction "1_P$1") (pintype "bidirectional"))
      (node (ref "VR1") (pin "2") (pinfunction "LX2_2") (pintype "bidirectional"))
    )
    (net (code "90") (name "Net-(L2-2)") (class "Default")
      (node (ref "L2") (pin "P$2") (pinfunction "2_P$2") (pintype "bidirectional"))
      (node (ref "VR1") (pin "8") (pinfunction "LX1_8") (pintype "bidirectional"))
    )
    (net (code "91") (name "Net-(L4-1)") (class "Default")
      (node (ref "C17") (pin "2") (pinfunction "2_2") (pintype "bidirectional"))
      (node (ref "C18") (pin "2") (pinfunction "2_2") (pintype "bidirectional"))
      (node (ref "C19") (pin "2") (pinfunction "2_2") (pintype "bidirectional"))
      (node (ref "L4") (pin "P$1") (pinfunction "1_P$1") (pintype "bidirectional"))
    )
    (net (code "92") (name "Net-(L4-2)") (class "Default")
      (node (ref "C10") (pin "2") (pinfunction "2_2") (pintype "bidirectional"))
      (node (ref "C16") (pin "2") (pinfunction "2_2") (pintype "bidirectional"))
      (node (ref "C21") (pin "2") (pinfunction "2_2") (pintype "bidirectional"))
      (node (ref "C39") (pin "2") (pinfunction "2_2") (pintype "bidirectional"))
      (node (ref "C9") (pin "2") (pinfunction "2_2") (pintype "bidirectional"))
      (node (ref "L4") (pin "P$2") (pinfunction "2_P$2") (pintype "bidirectional"))
      (node (ref "U4") (pin "19") (pinfunction "AC2_19") (pintype "bidirectional"))
    )
    (net (code "93") (name "Net-(L5-1)") (class "Default")
      (node (ref "L5") (pin "P$1") (pinfunction "1_P$1") (pintype "bidirectional"))
      (node (ref "U1") (pin "A1") (pinfunction "SIMOBUCK_SW_A1") (pintype "bidirectional"))
    )
    (net (code "94") (name "Net-(L5-2)") (class "Default")
      (node (ref "L5") (pin "P$2") (pinfunction "2_P$2") (pintype "bidirectional"))
      (node (ref "U1") (pin "A2") (pinfunction "SIMOBUCK_SWSEL_A2") (pintype "bidirectional"))
    )
    (net (code "95") (name "Net-(LS1-N)") (class "Default")
      (node (ref "D4") (pin "ANODE") (pinfunction "ANODE_ANODE") (pintype "bidirectional"))
      (node (ref "LS1") (pin "-") (pinfunction "N_-") (pintype "passive"))
      (node (ref "Q2") (pin "D") (pinfunction "D_D") (pintype "passive"))
    )
    (net (code "96") (name "Net-(R6-Pad1)") (class "Default")
      (node (ref "R6") (pin "1") (pinfunction "1_1") (pintype "passive"))
      (node (ref "R7") (pin "2") (pinfunction "2_2") (pintype "passive"))
    )
    (net (code "97") (name "Net-(R8-Pad2)") (class "Default")
      (node (ref "R8") (pin "2") (pinfunction "2_2") (pintype "passive"))
      (node (ref "R9") (pin "1") (pinfunction "1_1") (pintype "passive"))
    )
    (net (code "98") (name "Net-(R13-Pad1)") (class "Default")
      (node (ref "R13") (pin "1") (pinfunction "1_1") (pintype "passive"))
      (node (ref "RX14") (pin "2") (pinfunction "2_2") (pintype "passive"))
    )
    (net (code "99") (name "Net-(R13-Pad2)") (class "Default")
      (node (ref "R13") (pin "2") (pinfunction "2_2") (pintype "passive"))
      (node (ref "RT1") (pin "1") (pinfunction "1_1") (pintype "passive"))
    )
    (net (code "100") (name "Net-(R18-Pad2)") (class "Default")
      (node (ref "R18") (pin "2") (pinfunction "2_2") (pintype "passive"))
      (node (ref "R23") (pin "1") (pinfunction "1_1") (pintype "passive"))
    )
    (net (code "101") (name "Net-(S3A-OUT)") (class "Default")
      (node (ref "C33") (pin "1") (pinfunction "1_1") (pintype "bidirectional"))
      (node (ref "RZ1") (pin "1") (pinfunction "1_1") (pintype "passive"))
      (node (ref "S3") (pin "8") (pinfunction "OUT_8") (pintype "bidirectional"))
    )
    (net (code "102") (name "Net-(S3B-OUT)") (class "Default")
      (node (ref "C25") (pin "1") (pinfunction "1_1") (pintype "bidirectional"))
      (node (ref "RZ2") (pin "1") (pinfunction "1_1") (pintype "passive"))
      (node (ref "S3") (pin "5") (pinfunction "OUT_5") (pintype "bidirectional"))
    )
    (net (code "103") (name "Net-(SJ2-Pad1)") (class "Default")
      (node (ref "SJ2") (pin "1") (pinfunction "1_1") (pintype "passive"))
      (node (ref "XR19") (pin "2") (pinfunction "2_2") (pintype "passive"))
    )
    (net (code "104") (name "Net-(TP0-TESTPOINT)") (class "Default")
      (node (ref "TP0") (pin "P$1") (pinfunction "TESTPOINT_P$1") (pintype "bidirectional"))
      (node (ref "U2") (pin "C2") (pinfunction "GPIO0/RXOKLED_C2") (pintype "bidirectional"))
    )
    (net (code "105") (name "Net-(TP1-TESTPOINT)") (class "Default")
      (node (ref "TP1") (pin "P$1") (pinfunction "TESTPOINT_P$1") (pintype "bidirectional"))
      (node (ref "U2") (pin "D3") (pinfunction "GPIO1/SFDLED_D3") (pintype "bidirectional"))
    )
    (net (code "106") (name "Net-(TP2-TESTPOINT)") (class "Default")
      (node (ref "TP2") (pin "P$1") (pinfunction "TESTPOINT_P$1") (pintype "bidirectional"))
      (node (ref "U2") (pin "E4") (pinfunction "GPIO2/RXLED_E4") (pintype "bidirectional"))
    )
    (net (code "107") (name "Net-(TP3-TESTPOINT)") (class "Default")
      (node (ref "TP3") (pin "P$1") (pinfunction "TESTPOINT_P$1") (pintype "bidirectional"))
      (node (ref "U2") (pin "E2") (pinfunction "GPIO3/TXLED_E2") (pintype "bidirectional"))
    )
    (net (code "108") (name "Net-(TP4-TESTPOINT)") (class "Default")
      (node (ref "TP4") (pin "P$1") (pinfunction "TESTPOINT_P$1") (pintype "bidirectional"))
      (node (ref "U2") (pin "F1") (pinfunction "GPIO4/EXTPA_F1") (pintype "bidirectional"))
    )
    (net (code "109") (name "Net-(TP5-TESTPOINT)") (class "Default")
      (node (ref "TP5") (pin "P$1") (pinfunction "TESTPOINT_P$1") (pintype "bidirectional"))
      (node (ref "U2") (pin "D1") (pinfunction "GPIO5/EXTTXE/SPIPOL_D1") (pintype "bidirectional"))
    )
    (net (code "110") (name "Net-(U1-RFIOP)") (class "Default")
      (node (ref "CX5") (pin "1") (pinfunction "1_1") (pintype "passive"))
      (node (ref "L7") (pin "1") (pinfunction "1_1") (pintype "passive"))
      (node (ref "U1") (pin "M2") (pinfunction "RFIOP_M2") (pintype "bidirectional"))
    )
    (net (code "111") (name "Net-(U1-VDDBH_SW--BLE_BUCK_SW)") (class "Default")
      (node (ref "L6") (pin "1") (pinfunction "1_1") (pintype "bidirectional"))
      (node (ref "U1") (pin "H12") (pinfunction "VDDBH_SW--BLE_BUCK_SW_H12") (pintype "bidirectional"))
    )
    (net (code "112") (name "Net-(U1-XI)") (class "Default")
      (node (ref "C81") (pin "1") (pinfunction "1_1") (pintype "passive"))
      (node (ref "U1") (pin "A4") (pinfunction "XI_A4") (pintype "bidirectional"))
      (node (ref "X3") (pin "2") (pinfunction "2_2") (pintype "bidirectional"))
    )
    (net (code "113") (name "Net-(U1-XI32M)") (class "Default")
      (node (ref "CX4") (pin "1") (pinfunction "1_1") (pintype "passive"))
      (node (ref "U1") (pin "C12") (pinfunction "XI32M_C12") (pintype "bidirectional"))
      (node (ref "X1") (pin "3") (pinfunction "2_3") (pintype "bidirectional"))
    )
    (net (code "114") (name "Net-(U1-XO)") (class "Default")
      (node (ref "C80") (pin "1") (pinfunction "1_1") (pintype "passive"))
      (node (ref "U1") (pin "A5") (pinfunction "XO_A5") (pintype "bidirectional"))
      (node (ref "X3") (pin "1") (pinfunction "1_1") (pintype "bidirectional"))
    )
    (net (code "115") (name "Net-(U1-XO32M)") (class "Default")
      (node (ref "CX3") (pin "1") (pinfunction "1_1") (pintype "passive"))
      (node (ref "U1") (pin "D12") (pinfunction "XO32M_D12") (pintype "bidirectional"))
      (node (ref "X1") (pin "1") (pinfunction "1_1") (pintype "bidirectional"))
    )
    (net (code "116") (name "Net-(U2-RF2)") (class "Default")
      (node (ref "R1") (pin "1") (pinfunction "1_1") (pintype "passive"))
      (node (ref "U2") (pin "H5") (pinfunction "RF2_H5") (pintype "bidirectional"))
    )
    (net (code "117") (name "Net-(U2-VDD2A)") (class "Default")
      (node (ref "C12") (pin "P$1") (pinfunction "P$1_P$1") (pintype "bidirectional"))
      (node (ref "FB1") (pin "P$2") (pinfunction "P$2_P$2") (pintype "bidirectional"))
      (node (ref "U2") (pin "F15") (pinfunction "VDD2A_F15") (pintype "bidirectional"))
    )
    (net (code "118") (name "Net-(U2-VIO_D)") (class "Default")
      (node (ref "C23") (pin "1") (pinfunction "1_1") (pintype "bidirectional"))
      (node (ref "U2") (pin "A4") (pinfunction "VIO_D_A4") (pintype "bidirectional"))
    )
    (net (code "119") (name "Net-(U2-VTX_D)") (class "Default")
      (node (ref "C37") (pin "P$2") (pinfunction "P$2_P$2") (pintype "bidirectional"))
      (node (ref "U2") (pin "C14") (pinfunction "VTX_D_C14") (pintype "bidirectional"))
    )
    (net (code "120") (name "Net-(U2-XTI)") (class "Default")
      (node (ref "C3") (pin "P$1") (pinfunction "P$1_P$1") (pintype "bidirectional"))
      (node (ref "U2") (pin "H15") (pinfunction "XTI_H15") (pintype "bidirectional"))
      (node (ref "X4") (pin "1") (pinfunction "1_1") (pintype "bidirectional"))
    )
    (net (code "121") (name "Net-(U2-XTO)") (class "Default")
      (node (ref "C4") (pin "P$1") (pinfunction "P$1_P$1") (pintype "bidirectional"))
      (node (ref "U2") (pin "G14") (pinfunction "XTO_G14") (pintype "bidirectional"))
      (node (ref "X4") (pin "3") (pinfunction "2_3") (pintype "bidirectional"))
    )
    (net (code "122") (name "Net-(U3-ISET)") (class "Default")
      (node (ref "R15") (pin "2") (pinfunction "2_2") (pintype "passive"))
      (node (ref "U3") (pin "2") (pinfunction "ISET_2") (pintype "bidirectional"))
    )
    (net (code "123") (name "Net-(U3-PRETERM)") (class "Default")
      (node (ref "RX7") (pin "2") (pinfunction "2_2") (pintype "passive"))
      (node (ref "U3") (pin "4") (pinfunction "PRETERM_4") (pintype "bidirectional"))
    )
    (net (code "124") (name "Net-(U4-AC1)") (class "Default")
      (node (ref "C10") (pin "1") (pinfunction "1_1") (pintype "bidirectional"))
      (node (ref "C15") (pin "2") (pinfunction "2_2") (pintype "bidirectional"))
      (node (ref "C17") (pin "1") (pinfunction "1_1") (pintype "bidirectional"))
      (node (ref "C18") (pin "1") (pinfunction "1_1") (pintype "bidirectional"))
      (node (ref "C19") (pin "1") (pinfunction "1_1") (pintype "bidirectional"))
      (node (ref "C20") (pin "2") (pinfunction "2_2") (pintype "bidirectional"))
      (node (ref "C38") (pin "2") (pinfunction "2_2") (pintype "bidirectional"))
      (node (ref "C9") (pin "1") (pinfunction "1_1") (pintype "bidirectional"))
      (node (ref "U4") (pin "2") (pinfunction "AC1_2") (pintype "bidirectional"))
    )
    (net (code "125") (name "Net-(U4-BOOT1)") (class "Default")
      (node (ref "C15") (pin "1") (pinfunction "1_1") (pintype "bidirectional"))
      (node (ref "U4") (pin "3") (pinfunction "BOOT1_3") (pintype "bidirectional"))
    )
    (net (code "126") (name "Net-(U4-BOOT2)") (class "Default")
      (node (ref "C16") (pin "1") (pinfunction "1_1") (pintype "bidirectional"))
      (node (ref "U4") (pin "17") (pinfunction "BOOT2_17") (pintype "bidirectional"))
    )
    (net (code "127") (name "Net-(U4-CLAMP1)") (class "Default")
      (node (ref "C38") (pin "1") (pinfunction "1_1") (pintype "bidirectional"))
      (node (ref "U4") (pin "5") (pinfunction "CLAMP1_5") (pintype "bidirectional"))
    )
    (net (code "128") (name "Net-(U4-CLAMP2)") (class "Default")
      (node (ref "C39") (pin "1") (pinfunction "1_1") (pintype "bidirectional"))
      (node (ref "U4") (pin "16") (pinfunction "CLAMP2_16") (pintype "bidirectional"))
    )
    (net (code "129") (name "Net-(U4-COMM1)") (class "Default")
      (node (ref "C20") (pin "1") (pinfunction "1_1") (pintype "bidirectional"))
      (node (ref "U4") (pin "6") (pinfunction "COMM1_6") (pintype "bidirectional"))
    )
    (net (code "130") (name "Net-(U4-COMM2)") (class "Default")
      (node (ref "C21") (pin "1") (pinfunction "1_1") (pintype "bidirectional"))
      (node (ref "U4") (pin "15") (pinfunction "COMM2_15") (pintype "bidirectional"))
    )
    (net (code "131") (name "Net-(U4-FOD)") (class "Default")
      (node (ref "R23") (pin "2") (pinfunction "2_2") (pintype "passive"))
      (node (ref "R7") (pin "1") (pinfunction "1_1") (pintype "passive"))
      (node (ref "R9") (pin "2") (pinfunction "2_2") (pintype "passive"))
      (node (ref "U4") (pin "14") (pinfunction "FOD_14") (pintype "bidirectional"))
    )
    (net (code "132") (name "Net-(U4-ILIM)") (class "Default")
      (node (ref "R8") (pin "1") (pinfunction "1_1") (pintype "passive"))
      (node (ref "U4") (pin "12") (pinfunction "ILIM_12") (pintype "bidirectional"))
    )
    (net (code "133") (name "Net-(U4-RECT)") (class "Default")
      (node (ref "C28") (pin "1") (pinfunction "1_1") (pintype "bidirectional"))
      (node (ref "C56") (pin "1") (pinfunction "1_1") (pintype "bidirectional"))
      (node (ref "C57") (pin "1") (pinfunction "1_1") (pintype "bidirectional"))
      (node (ref "R18") (pin "1") (pinfunction "1_1") (pintype "passive"))
      (node (ref "U4") (pin "18") (pinfunction "RECT_18") (pintype "bidirectional"))
    )
    (net (code "134") (name "Net-(U6-CAP)") (class "Default")
      (node (ref "C36") (pin "1") (pinfunction "1_1") (pintype "bidirectional"))
      (node (ref "U6") (pin "9") (pinfunction "CAP_9") (pintype "bidirectional"))
    )
    (net (code "135") (name "Net-(U6-PS1)") (class "Default")
      (node (ref "SJ7") (pin "2") (pinfunction "2_2") (pintype "passive"))
      (node (ref "U6") (pin "5") (pinfunction "PS1_5") (pintype "input"))
    )
    (net (code "136") (name "Net-(U7-VCTRL)") (class "Default")
      (node (ref "SJ3") (pin "2") (pinfunction "2_2") (pintype "passive"))
      (node (ref "U7") (pin "8") (pinfunction "VCTRL_8") (pintype "bidirectional"))
    )
    (net (code "137") (name "Net-(U7-VDD)") (class "Default")
      (node (ref "C11") (pin "P$1") (pinfunction "P$1_P$1") (pintype "bidirectional"))
      (node (ref "C43") (pin "P$1") (pinfunction "P$1_P$1") (pintype "bidirectional"))
      (node (ref "RZ4") (pin "2") (pinfunction "2_2") (pintype "passive"))
      (node (ref "U7") (pin "1") (pinfunction "VDD_1") (pintype "bidirectional"))
    )
    (net (code "138") (name "Net-(VR2-EN)") (class "Default")
      (node (ref "RZ10") (pin "2") (pinfunction "2_2") (pintype "passive"))
      (node (ref "VR2") (pin "3") (pinfunction "EN_3") (pintype "input"))
    )
    (net (code "139") (name "Net-(XJ1-CC1)") (class "Default")
      (node (ref "XJ1") (pin "A5") (pinfunction "CC1_A5") (pintype "bidirectional"))
      (node (ref "XR16") (pin "1") (pinfunction "1_1") (pintype "passive"))
    )
    (net (code "140") (name "Net-(XJ1-CC2)") (class "Default")
      (node (ref "XJ1") (pin "B5") (pinfunction "CC2_B5") (pintype "bidirectional"))
      (node (ref "XR17") (pin "1") (pinfunction "1_1") (pintype "passive"))
    )
    (net (code "141") (name "RF1") (class "Default")
      (node (ref "S2") (pin "9") (pinfunction "J2_9") (pintype "bidirectional"))
      (node (ref "U7") (pin "6") (pinfunction "LNA_OUT_6") (pintype "bidirectional"))
    )
    (net (code "142") (name "RF2") (class "Default")
      (node (ref "A2") (pin "FEED") (pinfunction "ANTENNA_FEED") (pintype "bidirectional"))
      (node (ref "S2") (pin "3") (pinfunction "J3_3") (pintype "bidirectional"))
    )
    (net (code "143") (name "RF3") (class "Default")
      (node (ref "A3") (pin "FEED") (pinfunction "ANTENNA_FEED") (pintype "bidirectional"))
      (node (ref "S2") (pin "1") (pinfunction "J1_1") (pintype "bidirectional"))
      (node (ref "S4") (pin "IN") (pinfunction "IN_IN") (pintype "bidirectional"))
      (node (ref "S4") (pin "OUT") (pinfunction "A_OUT") (pintype "bidirectional"))
    )
    (net (code "144") (name "VBAT") (class "Default")
      (node (ref "C42") (pin "1") (pinfunction "1_1") (pintype "bidirectional"))
      (node (ref "J3") (pin "1") (pinfunction "1_1") (pintype "passive"))
      (node (ref "J4") (pin "3") (pinfunction "3_3") (pintype "bidirectional"))
      (node (ref "J4") (pin "3SUPP") (pinfunction "3_3SUPP") (pintype "bidirectional"))
      (node (ref "S1") (pin "2") (pinfunction "2_2") (pintype "passive"))
      (node (ref "U3") (pin "10") (pinfunction "OUT_10") (pintype "bidirectional"))
    )
    (net (code "145") (name "VBAT_SWITCHED") (class "Default")
      (node (ref "C45") (pin "2") (pinfunction "2_2") (pintype "bidirectional"))
      (node (ref "C48") (pin "1") (pinfunction "1_1") (pintype "bidirectional"))
      (node (ref "R31") (pin "2") (pinfunction "2_2") (pintype "passive"))
      (node (ref "R33") (pin "1") (pinfunction "1_1") (pintype "passive"))
      (node (ref "R34") (pin "1") (pinfunction "1_1") (pintype "passive"))
      (node (ref "S1") (pin "3") (pinfunction "3_3") (pintype "passive"))
      (node (ref "VR1") (pin "1") (pinfunction "VIN2_1") (pintype "bidirectional"))
      (node (ref "VR1") (pin "7") (pinfunction "VIN1_7") (pintype "bidirectional"))
    )
    (net (code "146") (name "VDDAUDA_1P8-CLEAN") (class "Default")
      (node (ref "C72") (pin "P$1") (pinfunction "1_P$1") (pintype "bidirectional"))
      (node (ref "RZ11") (pin "2") (pinfunction "2_2") (pintype "passive"))
      (node (ref "U1") (pin "B11") (pinfunction "VDDAUDA_B11") (pintype "bidirectional"))
    )
    (net (code "147") (name "VQI") (class "Default")
      (node (ref "C29") (pin "1") (pinfunction "1_1") (pintype "bidirectional"))
      (node (ref "C41") (pin "1") (pinfunction "1_1") (pintype "bidirectional"))
      (node (ref "C53") (pin "1") (pinfunction "1_1") (pintype "bidirectional"))
      (node (ref "Q1") (pin "A2") (pinfunction "D1_A2") (pintype "bidirectional"))
      (node (ref "Q1") (pin "A3") (pinfunction "D1_A3") (pintype "bidirectional"))
      (node (ref "Q1") (pin "B3") (pinfunction "D1_B3") (pintype "bidirectional"))
      (node (ref "U3") (pin "1") (pinfunction "IN_1") (pintype "bidirectional"))
      (node (ref "U4") (pin "4") (pinfunction "OUT_4") (pintype "bidirectional"))
    )
    (net (code "148") (name "VR1_1P8_EN") (class "Default")
      (node (ref "R34") (pin "2") (pinfunction "2_2") (pintype "passive"))
      (node (ref "VR1") (pin "6") (pinfunction "EN1_6") (pintype "bidirectional"))
    )
    (net (code "149") (name "VR1_2P5_EN") (class "Default")
      (node (ref "R33") (pin "2") (pinfunction "2_2") (pintype "passive"))
      (node (ref "VR1") (pin "12") (pinfunction "EN2_12") (pintype "bidirectional"))
    )
    (net (code "150") (name "VUSB") (class "Default")
      (node (ref "C40") (pin "2") (pinfunction "2_2") (pintype "bidirectional"))
      (node (ref "Q1") (pin "B2") (pinfunction "D2_B2") (pintype "bidirectional"))
      (node (ref "Q1") (pin "C2") (pinfunction "D2_C2") (pintype "bidirectional"))
      (node (ref "Q1") (pin "C3") (pinfunction "D2_C3") (pintype "bidirectional"))
      (node (ref "U4") (pin "9") (pinfunction "AD_9") (pintype "bidirectional"))
      (node (ref "XJ1") (pin "A4/B9") (pinfunction "VBUS_A4/B9") (pintype "power_in"))
      (node (ref "XJ1") (pin "B4/A9") (pinfunction "VBUS_B4/A9") (pintype "power_in"))
    )
    (net (code "151") (name "unconnected-(Q1-S-PadB1)") (class "Default")
      (node (ref "Q1") (pin "B1") (pinfunction "S_B1") (pintype "bidirectional"))
    )
    (net (code "152") (name "unconnected-(S1-Pad1)") (class "Default")
      (node (ref "S1") (pin "1") (pinfunction "1_1") (pintype "passive"))
    )
    (net (code "153") (name "unconnected-(U1-GPIO0-PadH3)") (class "Default")
      (node (ref "U1") (pin "H3") (pinfunction "GPIO0_H3") (pintype "bidirectional"))
    )
    (net (code "154") (name "unconnected-(U1-GPIO1-PadJ4)") (class "Default")
      (node (ref "U1") (pin "J4") (pinfunction "GPIO1_J4") (pintype "bidirectional"))
    )
    (net (code "155") (name "unconnected-(U1-GPIO2-PadK4)") (class "Default")
      (node (ref "U1") (pin "K4") (pinfunction "GPIO2_K4") (pintype "bidirectional"))
    )
    (net (code "156") (name "unconnected-(U1-GPIO4-PadM4)") (class "Default")
      (node (ref "U1") (pin "M4") (pinfunction "GPIO4_M4") (pintype "bidirectional"))
    )
    (net (code "157") (name "unconnected-(U1-GPIO5-PadH4)") (class "Default")
      (node (ref "U1") (pin "H4") (pinfunction "GPIO5_H4") (pintype "bidirectional"))
    )
    (net (code "158") (name "unconnected-(U1-GPIO7-PadJ6)") (class "Default")
      (node (ref "U1") (pin "J6") (pinfunction "GPIO7_J6") (pintype "bidirectional"))
    )
    (net (code "159") (name "unconnected-(U1-GPIO11-PadE4)") (class "Default")
      (node (ref "U1") (pin "E4") (pinfunction "GPIO11_E4") (pintype "bidirectional"))
    )
    (net (code "160") (name "unconnected-(U1-GPIO12-PadB4)") (class "Default")
      (node (ref "U1") (pin "B4") (pinfunction "GPIO12_B4") (pintype "bidirectional"))
    )
    (net (code "161") (name "unconnected-(U1-GPIO15-PadE5)") (class "Default")
      (node (ref "U1") (pin "E5") (pinfunction "GPIO15_E5") (pintype "bidirectional"))
    )
    (net (code "162") (name "unconnected-(U1-GPIO16-PadD7)") (class "Default")
      (node (ref "U1") (pin "D7") (pinfunction "GPIO16_D7") (pintype "bidirectional"))
    )
    (net (code "163") (name "unconnected-(U1-GPIO19-PadC3)") (class "Default")
      (node (ref "U1") (pin "C3") (pinfunction "GPIO19_C3") (pintype "bidirectional"))
    )
    (net (code "164") (name "unconnected-(U1-GPIO22-PadF3)") (class "Default")
      (node (ref "U1") (pin "F3") (pinfunction "GPIO22_F3") (pintype "bidirectional"))
    )
    (net (code "165") (name "unconnected-(U1-GPIO23-PadF2)") (class "Default")
      (node (ref "U1") (pin "F2") (pinfunction "GPIO23_F2") (pintype "bidirectional"))
    )
    (net (code "166") (name "unconnected-(U1-GPIO28-PadE3)") (class "Default")
      (node (ref "U1") (pin "E3") (pinfunction "GPIO28_E3") (pintype "bidirectional"))
    )
    (net (code "167") (name "unconnected-(U1-GPIO29-PadF4)") (class "Default")
      (node (ref "U1") (pin "F4") (pinfunction "GPIO29_F4") (pintype "bidirectional"))
    )
    (net (code "168") (name "unconnected-(U1-GPIO37-PadF11)") (class "Default")
      (node (ref "U1") (pin "F11") (pinfunction "GPIO37_F11") (pintype "bidirectional"))
    )
    (net (code "169") (name "unconnected-(U1-GPIO52-PadC10)") (class "Default")
      (node (ref "U1") (pin "C10") (pinfunction "GPIO52_C10") (pintype "bidirectional"))
    )
    (net (code "170") (name "unconnected-(U1-GPIO54-PadD10)") (class "Default")
      (node (ref "U1") (pin "D10") (pinfunction "GPIO54_D10") (pintype "bidirectional"))
    )
    (net (code "171") (name "unconnected-(U1-GPIO56-PadE10)") (class "Default")
      (node (ref "U1") (pin "E10") (pinfunction "GPIO56_E10") (pintype "bidirectional"))
    )
    (net (code "172") (name "unconnected-(U1-GPIO57-PadE9)") (class "Default")
      (node (ref "U1") (pin "E9") (pinfunction "GPIO57_E9") (pintype "bidirectional"))
    )
    (net (code "173") (name "unconnected-(U1-GPIO59-PadJ8)") (class "Default")
      (node (ref "U1") (pin "J8") (pinfunction "GPIO59_J8") (pintype "bidirectional"))
    )
    (net (code "174") (name "unconnected-(U1-GPIO61-PadK6)") (class "Default")
      (node (ref "U1") (pin "K6") (pinfunction "GPIO61_K6") (pintype "bidirectional"))
    )
    (net (code "175") (name "unconnected-(U1-GPIO62-PadL6)") (class "Default")
      (node (ref "U1") (pin "L6") (pinfunction "GPIO62_L6") (pintype "bidirectional"))
    )
    (net (code "176") (name "unconnected-(U1-GPIO64-PadB6)") (class "Default")
      (node (ref "U1") (pin "B6") (pinfunction "GPIO64_B6") (pintype "bidirectional"))
    )
    (net (code "177") (name "unconnected-(U1-GPIO67-PadC6)") (class "Default")
      (node (ref "U1") (pin "C6") (pinfunction "GPIO67_C6") (pintype "bidirectional"))
    )
    (net (code "178") (name "unconnected-(U1-GPIO68-PadB7)") (class "Default")
      (node (ref "U1") (pin "B7") (pinfunction "GPIO68_B7") (pintype "bidirectional"))
    )
    (net (code "179") (name "unconnected-(U1-GPIO70-PadC5)") (class "Default")
      (node (ref "U1") (pin "C5") (pinfunction "GPIO70_C5") (pintype "bidirectional"))
    )
    (net (code "180") (name "unconnected-(U1-GPIO71-PadC7)") (class "Default")
      (node (ref "U1") (pin "C7") (pinfunction "GPIO71_C7") (pintype "bidirectional"))
    )
    (net (code "181") (name "unconnected-(U1-GPIO73-PadD8)") (class "Default")
      (node (ref "U1") (pin "D8") (pinfunction "GPIO73_D8") (pintype "bidirectional"))
    )
    (net (code "182") (name "unconnected-(U1-GPIO74-PadG11)") (class "Default")
      (node (ref "U1") (pin "G11") (pinfunction "GPIO74_G11") (pintype "bidirectional"))
    )
    (net (code "183") (name "unconnected-(U1-GPIO75-PadH11)") (class "Default")
      (node (ref "U1") (pin "H11") (pinfunction "GPIO75_H11") (pintype "bidirectional"))
    )
    (net (code "184") (name "unconnected-(U1-GPIO76-PadJ11)") (class "Default")
      (node (ref "U1") (pin "J11") (pinfunction "GPIO76_J11") (pintype "bidirectional"))
    )
    (net (code "185") (name "unconnected-(U1-GPIO77-PadK11)") (class "Default")
      (node (ref "U1") (pin "K11") (pinfunction "GPIO77_K11") (pintype "bidirectional"))
    )
    (net (code "186") (name "unconnected-(U1-GPIO78-PadL11)") (class "Default")
      (node (ref "U1") (pin "L11") (pinfunction "GPIO78_L11") (pintype "bidirectional"))
    )
    (net (code "187") (name "unconnected-(U1-GPIO84-PadJ9)") (class "Default")
      (node (ref "U1") (pin "J9") (pinfunction "GPIO84_J9") (pintype "bidirectional"))
    )
    (net (code "188") (name "unconnected-(U1-GPIO85-PadH9)") (class "Default")
      (node (ref "U1") (pin "H9") (pinfunction "GPIO85_H9") (pintype "bidirectional"))
    )
    (net (code "189") (name "unconnected-(U1-GPIO86-PadG10)") (class "Default")
      (node (ref "U1") (pin "G10") (pinfunction "GPIO86_G10") (pintype "bidirectional"))
    )
    (net (code "190") (name "unconnected-(U1-GPIO87-PadG9)") (class "Default")
      (node (ref "U1") (pin "G9") (pinfunction "GPIO87_G9") (pintype "bidirectional"))
    )
    (net (code "191") (name "unconnected-(U1-GPIO89-PadF10)") (class "Default")
      (node (ref "U1") (pin "F10") (pinfunction "GPIO89_F10") (pintype "bidirectional"))
    )
    (net (code "192") (name "unconnected-(U1-GPIO90-PadJ2)") (class "Default")
      (node (ref "U1") (pin "J2") (pinfunction "GPIO90_J2") (pintype "bidirectional"))
    )
    (net (code "193") (name "unconnected-(U1-GPIO91-PadK2)") (class "Default")
      (node (ref "U1") (pin "K2") (pinfunction "GPIO91_K2") (pintype "bidirectional"))
    )
    (net (code "194") (name "unconnected-(U1-LPADC_D0NSE0-PadA10)") (class "Default")
      (node (ref "U1") (pin "A10") (pinfunction "LPADC_D0NSE0_A10") (pintype "input"))
    )
    (net (code "195") (name "unconnected-(U1-LPADC_D0PSE1-PadA11)") (class "Default")
      (node (ref "U1") (pin "A11") (pinfunction "LPADC_D0PSE1_A11") (pintype "input"))
    )
    (net (code "196") (name "unconnected-(U1-LPADC_D1NSE2-PadC11)") (class "Default")
      (node (ref "U1") (pin "C11") (pinfunction "LPADC_D1NSE2_C11") (pintype "input"))
    )
    (net (code "197") (name "unconnected-(U1-LPADC_D1PSE3-PadD11)") (class "Default")
      (node (ref "U1") (pin "D11") (pinfunction "LPADC_D1PSE3_D11") (pintype "input"))
    )
    (net (code "198") (name "unconnected-(U1-MIPI_CLKN-PadJ12)") (class "Default")
      (node (ref "U1") (pin "J12") (pinfunction "MIPI_CLKN_J12") (pintype "bidirectional"))
    )
    (net (code "199") (name "unconnected-(U1-MIPI_CLKP-PadK12)") (class "Default")
      (node (ref "U1") (pin "K12") (pinfunction "MIPI_CLKP_K12") (pintype "bidirectional"))
    )
    (net (code "200") (name "unconnected-(U1-MIPI_DON-PadL12)") (class "Default")
      (node (ref "U1") (pin "L12") (pinfunction "MIPI_DON_L12") (pintype "bidirectional"))
    )
    (net (code "201") (name "unconnected-(U1-MIPI_DOP-PadM12)") (class "Default")
      (node (ref "U1") (pin "M12") (pinfunction "MIPI_DOP_M12") (pintype "bidirectional"))
    )
    (net (code "202") (name "unconnected-(U1-TXEN-PadK1)") (class "Default")
      (node (ref "U1") (pin "K1") (pinfunction "TXEN_K1") (pintype "output"))
    )
    (net (code "203") (name "unconnected-(VR1-NC1-Pad5)") (class "Default")
      (node (ref "VR1") (pin "5") (pinfunction "NC1_5") (pintype "bidirectional"))
    )
    (net (code "204") (name "unconnected-(VR1-NC2-Pad11)") (class "Default")
      (node (ref "VR1") (pin "11") (pinfunction "NC2_11") (pintype "bidirectional"))
    )
    (net (code "205") (name "unconnected-(XJ1-SBU1-PadA8)") (class "Default")
      (node (ref "XJ1") (pin "A8") (pinfunction "SBU1_A8") (pintype "bidirectional"))
    )
    (net (code "206") (name "unconnected-(XJ1-SBU2-PadB8)") (class "Default")
      (node (ref "XJ1") (pin "B8") (pinfunction "SBU2_B8") (pintype "bidirectional"))
    )
    (net (code "207") (name "~{AD_EN}") (class "Default")
      (node (ref "Q1") (pin "A1") (pinfunction "G1_A1") (pintype "input"))
      (node (ref "Q1") (pin "C1") (pinfunction "G2_C1") (pintype "input"))
      (node (ref "U4") (pin "8") (pinfunction "~{AD-EN}_8") (pintype "bidirectional"))
    )
  )
)
